# Presentation_PCB.net
KiCad netlist of a schematic drawn in EAGLE
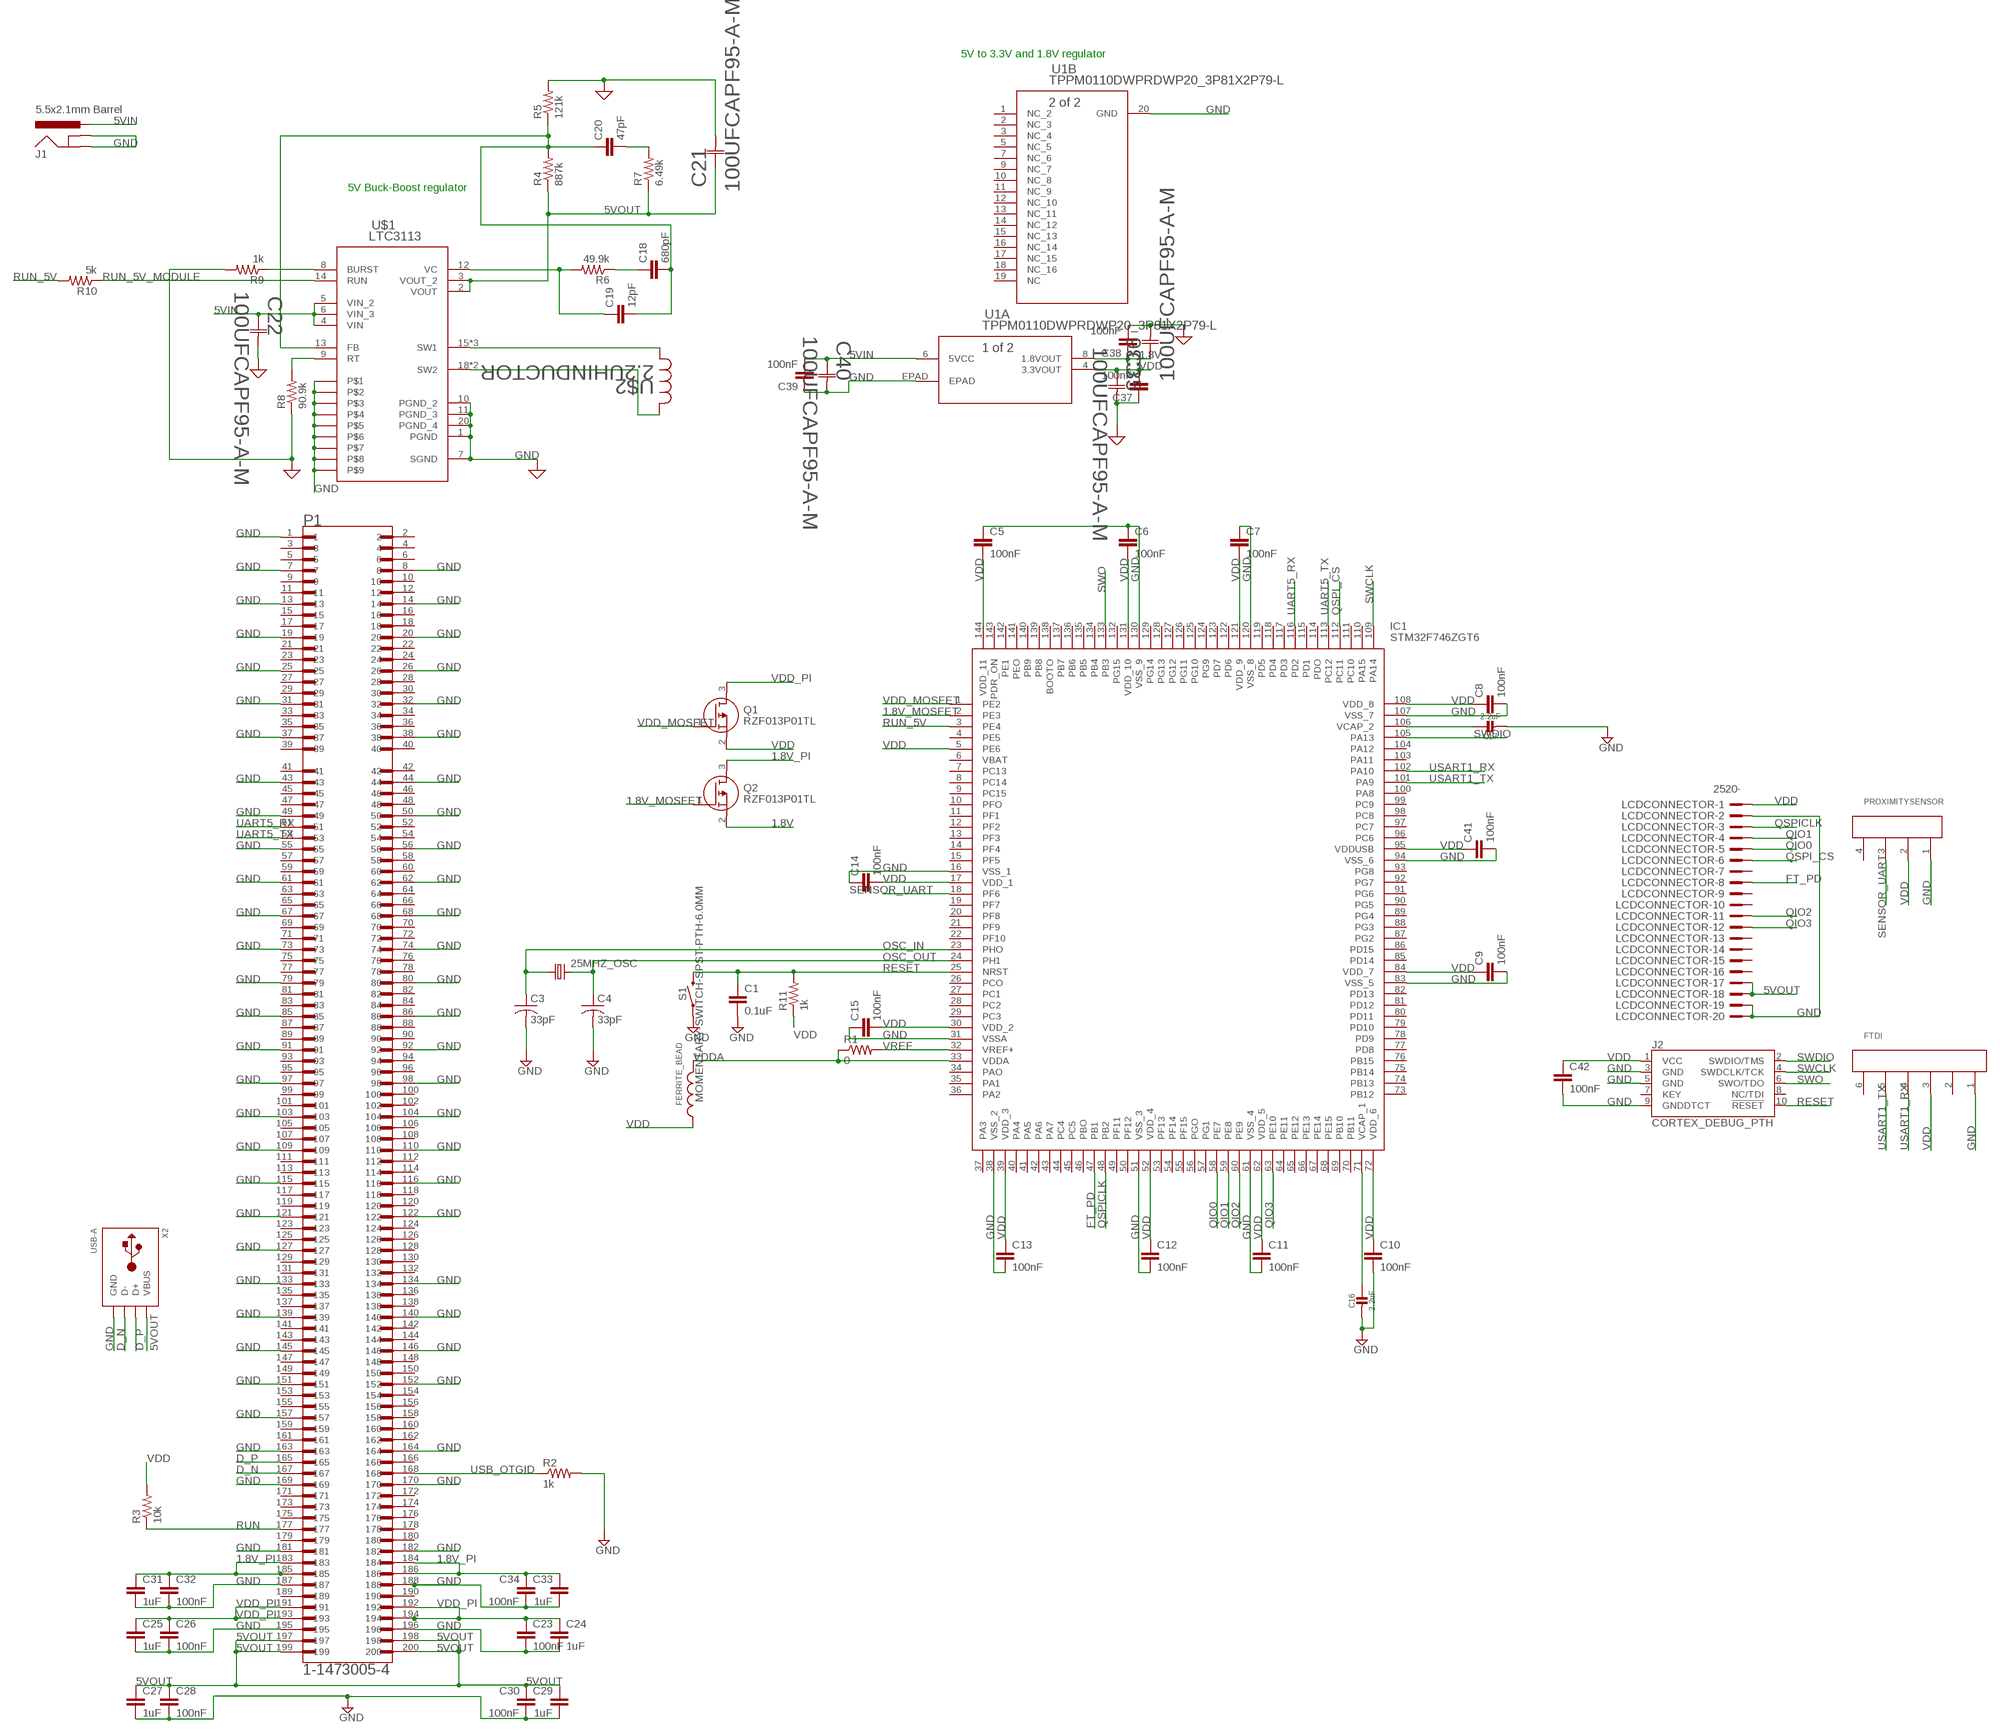
[diagram p0: schematic, sheet 1]

(export (version "E")
  (design (tool "Eeschema 10.0.6"))
  (components
    (comp (ref "25MHZ_OSC")
      (value "CRYSTALHC49UP")
      (footprint "eagle-import:HC49UP")
      (libsource (lib "eagle-import") (part "CRYSTALHC49UP"))
    )
    (comp (ref "C1")
      (value "0.1uF")
      (footprint "eagle-import:C0805")
      (libsource (lib "eagle-import") (part "C-EUC0805"))
    )
    (comp (ref "C3")
      (value "33pF")
      (footprint "eagle-import:C0805")
      (libsource (lib "eagle-import") (part "C-USC0805"))
    )
    (comp (ref "C4")
      (value "33pF")
      (footprint "eagle-import:C0805")
      (libsource (lib "eagle-import") (part "C-USC0805"))
    )
    (comp (ref "C5")
      (value "100nF")
      (footprint "eagle-import:C0805")
      (libsource (lib "eagle-import") (part "C-EUC0805"))
    )
    (comp (ref "C6")
      (value "100nF")
      (footprint "eagle-import:C0805")
      (libsource (lib "eagle-import") (part "C-EUC0805"))
    )
    (comp (ref "C7")
      (value "100nF")
      (footprint "eagle-import:C0805")
      (libsource (lib "eagle-import") (part "C-EUC0805"))
    )
    (comp (ref "C8")
      (value "100nF")
      (footprint "eagle-import:C0805")
      (libsource (lib "eagle-import") (part "C-EUC0805"))
    )
    (comp (ref "C9")
      (value "100nF")
      (footprint "eagle-import:C0805")
      (libsource (lib "eagle-import") (part "C-EUC0805"))
    )
    (comp (ref "C10")
      (value "100nF")
      (footprint "eagle-import:C0805")
      (libsource (lib "eagle-import") (part "C-EUC0805"))
    )
    (comp (ref "C11")
      (value "100nF")
      (footprint "eagle-import:C0805")
      (libsource (lib "eagle-import") (part "C-EUC0805"))
    )
    (comp (ref "C12")
      (value "100nF")
      (footprint "eagle-import:C0805")
      (libsource (lib "eagle-import") (part "C-EUC0805"))
    )
    (comp (ref "C13")
      (value "100nF")
      (footprint "eagle-import:C0805")
      (libsource (lib "eagle-import") (part "C-EUC0805"))
    )
    (comp (ref "C14")
      (value "100nF")
      (footprint "eagle-import:C0805")
      (libsource (lib "eagle-import") (part "C-EUC0805"))
    )
    (comp (ref "C15")
      (value "100nF")
      (footprint "eagle-import:C0805")
      (libsource (lib "eagle-import") (part "C-EUC0805"))
    )
    (comp (ref "C16")
      (value "2.2uF")
      (footprint "eagle-import:0805-NO")
      (libsource (lib "eagle-import") (part "CAP_CERAMIC0805-NOOUTLINE"))
    )
    (comp (ref "C17")
      (value "2.2uF")
      (footprint "eagle-import:0805-NO")
      (libsource (lib "eagle-import") (part "CAP_CERAMIC0805-NOOUTLINE"))
    )
    (comp (ref "C18")
      (value "680pF")
      (footprint "eagle-import:C0805")
      (libsource (lib "eagle-import") (part "C-EUC0805"))
    )
    (comp (ref "C19")
      (value "12pF")
      (footprint "eagle-import:C0805")
      (libsource (lib "eagle-import") (part "C-EUC0805"))
    )
    (comp (ref "C20")
      (value "47pF")
      (footprint "eagle-import:C0805")
      (libsource (lib "eagle-import") (part "C-EUC0805"))
    )
    (comp (ref "C21")
      (value "100UFCAPF95-A-M")
      (footprint "eagle-import:F95-A-M")
      (fields (field (name "MANUFACTURER_PART_NUMBER") "F951A107KAAAQ2"))
      (libsource (lib "eagle-import") (part "100UFCAPF95-A-M"))
    )
    (comp (ref "C22")
      (value "100UFCAPF95-A-M")
      (footprint "eagle-import:F95-A-M")
      (fields (field (name "MANUFACTURER_PART_NUMBER") "F951A107KAAAQ2"))
      (libsource (lib "eagle-import") (part "100UFCAPF95-A-M"))
    )
    (comp (ref "C23")
      (value "100nF")
      (footprint "eagle-import:C0805")
      (libsource (lib "eagle-import") (part "C-EUC0805"))
    )
    (comp (ref "C24")
      (value "1uF")
      (footprint "eagle-import:C0805")
      (libsource (lib "eagle-import") (part "C-EUC0805"))
    )
    (comp (ref "C25")
      (value "1uF")
      (footprint "eagle-import:C0805")
      (libsource (lib "eagle-import") (part "C-EUC0805"))
    )
    (comp (ref "C26")
      (value "100nF")
      (footprint "eagle-import:C0805")
      (libsource (lib "eagle-import") (part "C-EUC0805"))
    )
    (comp (ref "C27")
      (value "1uF")
      (footprint "eagle-import:C0805")
      (libsource (lib "eagle-import") (part "C-EUC0805"))
    )
    (comp (ref "C28")
      (value "100nF")
      (footprint "eagle-import:C0805")
      (libsource (lib "eagle-import") (part "C-EUC0805"))
    )
    (comp (ref "C29")
      (value "1uF")
      (footprint "eagle-import:C0805")
      (libsource (lib "eagle-import") (part "C-EUC0805"))
    )
    (comp (ref "C30")
      (value "100nF")
      (footprint "eagle-import:C0805")
      (libsource (lib "eagle-import") (part "C-EUC0805"))
    )
    (comp (ref "C31")
      (value "1uF")
      (footprint "eagle-import:C0805")
      (libsource (lib "eagle-import") (part "C-EUC0805"))
    )
    (comp (ref "C32")
      (value "100nF")
      (footprint "eagle-import:C0805")
      (libsource (lib "eagle-import") (part "C-EUC0805"))
    )
    (comp (ref "C33")
      (value "1uF")
      (footprint "eagle-import:C0805")
      (libsource (lib "eagle-import") (part "C-EUC0805"))
    )
    (comp (ref "C34")
      (value "100nF")
      (footprint "eagle-import:C0805")
      (libsource (lib "eagle-import") (part "C-EUC0805"))
    )
    (comp (ref "C35")
      (value "100UFCAPF95-A-M")
      (footprint "eagle-import:F95-A-M")
      (fields (field (name "MANUFACTURER_PART_NUMBER") "F951A107KAAAQ2"))
      (libsource (lib "eagle-import") (part "100UFCAPF95-A-M"))
    )
    (comp (ref "C36")
      (value "100UFCAPF95-A-M")
      (footprint "eagle-import:F95-A-M")
      (fields (field (name "MANUFACTURER_PART_NUMBER") "F951A107KAAAQ2"))
      (libsource (lib "eagle-import") (part "100UFCAPF95-A-M"))
    )
    (comp (ref "C37")
      (value "100nF")
      (footprint "eagle-import:C0805")
      (libsource (lib "eagle-import") (part "C-EUC0805"))
    )
    (comp (ref "C38")
      (value "100nF")
      (footprint "eagle-import:C0805")
      (libsource (lib "eagle-import") (part "C-EUC0805"))
    )
    (comp (ref "C39")
      (value "100nF")
      (footprint "eagle-import:C0805")
      (libsource (lib "eagle-import") (part "C-EUC0805"))
    )
    (comp (ref "C40")
      (value "100UFCAPF95-A-M")
      (footprint "eagle-import:F95-A-M")
      (fields (field (name "MANUFACTURER_PART_NUMBER") "F951A107KAAAQ2"))
      (libsource (lib "eagle-import") (part "100UFCAPF95-A-M"))
    )
    (comp (ref "C41")
      (value "100nF")
      (footprint "eagle-import:C0805")
      (libsource (lib "eagle-import") (part "C-EUC0805"))
    )
    (comp (ref "C42")
      (value "100nF")
      (footprint "eagle-import:C0805")
      (libsource (lib "eagle-import") (part "C-EUC0805"))
    )
    (comp (ref "FERRITE_BEAD")
      (value "WE-CBA_0805_782853112_HC")
      (footprint "eagle-import:WE-CBA_0805(W=4)")
      (libsource (lib "eagle-import") (part "WE-CBA_0805_HC_782853112"))
    )
    (comp (ref "FTDI")
      (value "66100611622")
      (footprint "eagle-import:66100611622")
      (libsource (lib "eagle-import") (part "66100611622"))
    )
    (comp (ref "IC1")
      (value "STM32F746ZGT6")
      (footprint "eagle-import:QFP50P2200X2200X160-144N")
      (fields
        (field (name "MOUSER_PART_NUMBER") "511-STM32F746ZGT6")
        (field (name "RS_PART_NUMBER") "8820290")
      )
      (libsource (lib "eagle-import") (part "STM32F746ZGT6"))
    )
    (comp (ref "J1")
      (value "5.5x2.1mm Barrel")
      (footprint "eagle-import:POWER_JACK_SMD")
      (libsource (lib "eagle-import") (part "POWER_JACKSMD"))
    )
    (comp (ref "J2")
      (value "CORTEX_DEBUG_PTH")
      (footprint "eagle-import:2X5-PTH-1.27MM")
      (libsource (lib "eagle-import") (part "CORTEX_DEBUG_PTH"))
    )
    (comp (ref "LCDCONNECTOR")
      (value "2520-")
      (footprint "eagle-import:PAK100_2500-20")
      (libsource (lib "eagle-import") (part "2520-"))
    )
    (comp (ref "P1")
      (value "1-1473005-4")
      (footprint "eagle-import:TE_1-1473005-4")
      (fields (field (name "MF") "TE Connectivity"))
      (libsource (lib "eagle-import") (part "1-1473005-4"))
    )
    (comp (ref "PROXIMITYSENSOR")
      (value "66100411622")
      (footprint "eagle-import:66100411622")
      (libsource (lib "eagle-import") (part "66100411622"))
    )
    (comp (ref "Q1")
      (value "RZF013P01TL")
      (footprint "eagle-import:SOT65P210X85-3N")
      (fields (field (name "MOUSER_PART_NUMBER") "755-RZF013P01TL"))
      (libsource (lib "eagle-import") (part "RZF013P01TL"))
    )
    (comp (ref "Q2")
      (value "RZF013P01TL")
      (footprint "eagle-import:SOT65P210X85-3N")
      (fields (field (name "MOUSER_PART_NUMBER") "755-RZF013P01TL"))
      (libsource (lib "eagle-import") (part "RZF013P01TL"))
    )
    (comp (ref "R1")
      (value "0")
      (footprint "eagle-import:R0805")
      (libsource (lib "eagle-import") (part "R-US_R0805"))
    )
    (comp (ref "R2")
      (value "1k")
      (footprint "eagle-import:R0805")
      (libsource (lib "eagle-import") (part "R-US_R0805"))
    )
    (comp (ref "R3")
      (value "10k")
      (footprint "eagle-import:R0805")
      (libsource (lib "eagle-import") (part "R-US_R0805"))
    )
    (comp (ref "R4")
      (value "887k")
      (footprint "eagle-import:R0805")
      (libsource (lib "eagle-import") (part "resistor_348_R-US_R0805"))
    )
    (comp (ref "R5")
      (value "121k")
      (footprint "eagle-import:R0805")
      (libsource (lib "eagle-import") (part "resistor_348_R-US_R0805"))
    )
    (comp (ref "R6")
      (value "49.9k")
      (footprint "eagle-import:R0805")
      (libsource (lib "eagle-import") (part "resistor_348_R-US_R0805"))
    )
    (comp (ref "R7")
      (value "6.49k")
      (footprint "eagle-import:R0805")
      (libsource (lib "eagle-import") (part "resistor_348_R-US_R0805"))
    )
    (comp (ref "R8")
      (value "90.9k")
      (footprint "eagle-import:R0805")
      (libsource (lib "eagle-import") (part "resistor_348_R-US_R0805"))
    )
    (comp (ref "R9")
      (value "1k")
      (footprint "eagle-import:R0805")
      (libsource (lib "eagle-import") (part "resistor_348_R-US_R0805"))
    )
    (comp (ref "R10")
      (value "5k")
      (footprint "eagle-import:R0805")
      (libsource (lib "eagle-import") (part "resistor_348_R-US_R0805"))
    )
    (comp (ref "R11")
      (value "1k")
      (footprint "eagle-import:R0805")
      (libsource (lib "eagle-import") (part "R-US_R0805"))
    )
    (comp (ref "S1")
      (value "MOMENTARY-SWITCH-SPST-PTH-6.0MM")
      (footprint "eagle-import:TACTILE_SWITCH_PTH_6.0MM")
      (libsource (lib "eagle-import") (part "MOMENTARY-SWITCH-SPST-PTH-6.0MM"))
    )
    (comp (ref "U$1")
      (value "LTC3113")
      (footprint "eagle-import:TSSOP-20_FE_CA")
      (libsource (lib "eagle-import") (part "LTC3113"))
    )
    (comp (ref "U$2")
      (value "2.2UHINDUCTOR")
      (footprint "eagle-import:IND_10040")
      (libsource (lib "eagle-import") (part "2.2UHINDUCTOR"))
    )
    (comp (ref "U1")
      (value "TPPM0110DWPRDWP20_3P81X2P79-L")
      (footprint "eagle-import:DWP20_3P81X2P79-L")
      (fields (field (name "MANUFACTURER_PART_NUMBER") "TPPM0110DWPR"))
      (libsource (lib "eagle-import") (part "TPPM0110DWPRDWP20_3P81X2P79-L"))
    )
    (comp (ref "X2")
      (value "USB-A")
      (footprint "eagle-import:MOLEX_480371000")
      (libsource (lib "eagle-import") (part "USB-A"))
    )
  )
  (nets
    (net (code "1") (name "/1.8V") (class "Default")
      (node (ref "C36") (pin "1") (pinfunction "1_1") (pintype "passive"))
      (node (ref "C38") (pin "1") (pinfunction "1_1") (pintype "passive"))
      (node (ref "Q2") (pin "2") (pinfunction "S_2") (pintype "bidirectional"))
      (node (ref "U1") (pin "8") (pinfunction "1.8VOUT_8") (pintype "output"))
    )
    (net (code "2") (name "/1.8V_MOSFET") (class "Default")
      (node (ref "IC1") (pin "2") (pinfunction "PE3_2") (pintype "bidirectional"))
      (node (ref "Q2") (pin "1") (pinfunction "G_1") (pintype "bidirectional"))
    )
    (net (code "3") (name "/1.8V_PI") (class "Default")
      (node (ref "C31") (pin "1") (pinfunction "1_1") (pintype "passive"))
      (node (ref "C32") (pin "1") (pinfunction "1_1") (pintype "passive"))
      (node (ref "C33") (pin "1") (pinfunction "1_1") (pintype "passive"))
      (node (ref "C34") (pin "1") (pinfunction "1_1") (pintype "passive"))
      (node (ref "P1") (pin "183") (pinfunction "183_183") (pintype "passive"))
      (node (ref "P1") (pin "184") (pinfunction "184_184") (pintype "passive"))
      (node (ref "P1") (pin "185") (pinfunction "185_185") (pintype "passive"))
      (node (ref "P1") (pin "186") (pinfunction "186_186") (pintype "passive"))
      (node (ref "Q2") (pin "3") (pinfunction "D_3") (pintype "bidirectional"))
    )
    (net (code "4") (name "/5VIN") (class "Default")
      (node (ref "C22") (pin "1") (pinfunction "1_1") (pintype "passive"))
      (node (ref "C39") (pin "2") (pinfunction "2_2") (pintype "passive"))
      (node (ref "C40") (pin "1") (pinfunction "1_1") (pintype "passive"))
      (node (ref "J1") (pin "VIN0") (pinfunction "PWR_VIN0") (pintype "bidirectional"))
      (node (ref "U$1") (pin "4") (pinfunction "VIN_4") (pintype "passive"))
      (node (ref "U$1") (pin "5") (pinfunction "VIN_2_5") (pintype "passive"))
      (node (ref "U$1") (pin "6") (pinfunction "VIN_3_6") (pintype "passive"))
      (node (ref "U1") (pin "6") (pinfunction "5VCC_6") (pintype "input"))
    )
    (net (code "5") (name "/5VOUT") (class "Default")
      (node (ref "C21") (pin "1") (pinfunction "1_1") (pintype "passive"))
      (node (ref "C27") (pin "1") (pinfunction "1_1") (pintype "passive"))
      (node (ref "C28") (pin "1") (pinfunction "1_1") (pintype "passive"))
      (node (ref "C29") (pin "1") (pinfunction "1_1") (pintype "passive"))
      (node (ref "C30") (pin "1") (pinfunction "1_1") (pintype "passive"))
      (node (ref "LCDCONNECTOR") (pin "17") (pinfunction "KL_17") (pintype "passive"))
      (node (ref "LCDCONNECTOR") (pin "18") (pinfunction "KL_18") (pintype "passive"))
      (node (ref "P1") (pin "197") (pinfunction "197_197") (pintype "passive"))
      (node (ref "P1") (pin "198") (pinfunction "198_198") (pintype "passive"))
      (node (ref "P1") (pin "199") (pinfunction "199_199") (pintype "passive"))
      (node (ref "P1") (pin "200") (pinfunction "200_200") (pintype "passive"))
      (node (ref "R4") (pin "1") (pinfunction "1_1") (pintype "passive"))
      (node (ref "R7") (pin "1") (pinfunction "1_1") (pintype "passive"))
      (node (ref "U$1") (pin "2") (pinfunction "VOUT_2") (pintype "passive"))
      (node (ref "U$1") (pin "3") (pinfunction "VOUT_2_3") (pintype "passive"))
      (node (ref "X2") (pin "1") (pinfunction "VBUS_1") (pintype "power_in"))
    )
    (net (code "6") (name "/D_N") (class "Default")
      (node (ref "P1") (pin "167") (pinfunction "167_167") (pintype "passive"))
      (node (ref "X2") (pin "2") (pinfunction "D-_2") (pintype "bidirectional"))
    )
    (net (code "7") (name "/D_P") (class "Default")
      (node (ref "P1") (pin "165") (pinfunction "165_165") (pintype "passive"))
      (node (ref "X2") (pin "3") (pinfunction "D+_3") (pintype "bidirectional"))
    )
    (net (code "8") (name "/FT_PD") (class "Default")
      (node (ref "IC1") (pin "47") (pinfunction "PB1_47") (pintype "bidirectional"))
      (node (ref "LCDCONNECTOR") (pin "8") (pinfunction "KL_8") (pintype "passive"))
    )
    (net (code "9") (name "/OSC_IN") (class "Default")
      (node (ref "25MHZ_OSC") (pin "1") (pinfunction "1_1") (pintype "passive"))
      (node (ref "C3") (pin "1") (pinfunction "1_1") (pintype "passive"))
      (node (ref "IC1") (pin "23") (pinfunction "PHO_23") (pintype "bidirectional"))
    )
    (net (code "10") (name "/OSC_OUT") (class "Default")
      (node (ref "25MHZ_OSC") (pin "2") (pinfunction "2_2") (pintype "passive"))
      (node (ref "C4") (pin "1") (pinfunction "1_1") (pintype "passive"))
      (node (ref "IC1") (pin "24") (pinfunction "PH1_24") (pintype "bidirectional"))
    )
    (net (code "11") (name "/QIO0") (class "Default")
      (node (ref "IC1") (pin "58") (pinfunction "PE7_58") (pintype "bidirectional"))
      (node (ref "LCDCONNECTOR") (pin "5") (pinfunction "KL_5") (pintype "passive"))
    )
    (net (code "12") (name "/QIO1") (class "Default")
      (node (ref "IC1") (pin "59") (pinfunction "PE8_59") (pintype "bidirectional"))
      (node (ref "LCDCONNECTOR") (pin "4") (pinfunction "KL_4") (pintype "passive"))
    )
    (net (code "13") (name "/QIO2") (class "Default")
      (node (ref "IC1") (pin "60") (pinfunction "PE9_60") (pintype "bidirectional"))
      (node (ref "LCDCONNECTOR") (pin "11") (pinfunction "KL_11") (pintype "passive"))
    )
    (net (code "14") (name "/QIO3") (class "Default")
      (node (ref "IC1") (pin "63") (pinfunction "PE10_63") (pintype "bidirectional"))
      (node (ref "LCDCONNECTOR") (pin "12") (pinfunction "KL_12") (pintype "passive"))
    )
    (net (code "15") (name "/QSPICLK") (class "Default")
      (node (ref "IC1") (pin "48") (pinfunction "PB2_48") (pintype "bidirectional"))
      (node (ref "LCDCONNECTOR") (pin "3") (pinfunction "KL_3") (pintype "passive"))
    )
    (net (code "16") (name "/QSPI_CS") (class "Default")
      (node (ref "IC1") (pin "112") (pinfunction "PC11_112") (pintype "bidirectional"))
      (node (ref "LCDCONNECTOR") (pin "6") (pinfunction "KL_6") (pintype "passive"))
    )
    (net (code "17") (name "/RESET") (class "Default")
      (node (ref "C1") (pin "1") (pinfunction "1_1") (pintype "passive"))
      (node (ref "IC1") (pin "25") (pinfunction "NRST_25") (pintype "input"))
      (node (ref "J2") (pin "10") (pinfunction "~{RESET}_10") (pintype "bidirectional"))
      (node (ref "R11") (pin "2") (pinfunction "2_2") (pintype "passive"))
      (node (ref "S1") (pin "3") (pinfunction "2_3") (pintype "passive"))
    )
    (net (code "18") (name "/RUN") (class "Default")
      (node (ref "P1") (pin "177") (pinfunction "177_177") (pintype "passive"))
      (node (ref "R3") (pin "1") (pinfunction "1_1") (pintype "passive"))
    )
    (net (code "19") (name "/RUN_5V") (class "Default")
      (node (ref "IC1") (pin "3") (pinfunction "PE4_3") (pintype "bidirectional"))
      (node (ref "R10") (pin "2") (pinfunction "2_2") (pintype "passive"))
    )
    (net (code "20") (name "/RUN_5V_MODULE") (class "Default")
      (node (ref "R10") (pin "1") (pinfunction "1_1") (pintype "passive"))
      (node (ref "U$1") (pin "14") (pinfunction "RUN_14") (pintype "passive"))
    )
    (net (code "21") (name "/SENSOR_UART") (class "Default")
      (node (ref "IC1") (pin "18") (pinfunction "PF6_18") (pintype "bidirectional"))
      (node (ref "PROXIMITYSENSOR") (pin "3") (pinfunction "3_3") (pintype "passive"))
    )
    (net (code "22") (name "/SWCLK") (class "Default")
      (node (ref "IC1") (pin "109") (pinfunction "PA14_109") (pintype "bidirectional"))
      (node (ref "J2") (pin "4") (pinfunction "SWDCLK/TCK_4") (pintype "bidirectional"))
    )
    (net (code "23") (name "/SWDIO") (class "Default")
      (node (ref "IC1") (pin "105") (pinfunction "PA13_105") (pintype "bidirectional"))
      (node (ref "J2") (pin "2") (pinfunction "SWDIO/TMS_2") (pintype "bidirectional"))
    )
    (net (code "24") (name "/SWO") (class "Default")
      (node (ref "IC1") (pin "133") (pinfunction "PB3_133") (pintype "bidirectional"))
      (node (ref "J2") (pin "6") (pinfunction "SWO/TDO_6") (pintype "bidirectional"))
    )
    (net (code "25") (name "/UART5_RX") (class "Default")
      (node (ref "IC1") (pin "116") (pinfunction "PD2_116") (pintype "bidirectional"))
      (node (ref "P1") (pin "51") (pinfunction "51_51") (pintype "passive"))
    )
    (net (code "26") (name "/UART5_TX") (class "Default")
      (node (ref "IC1") (pin "113") (pinfunction "PC12_113") (pintype "bidirectional"))
      (node (ref "P1") (pin "53") (pinfunction "53_53") (pintype "passive"))
    )
    (net (code "27") (name "/USART1_RX") (class "Default")
      (node (ref "FTDI") (pin "4") (pinfunction "4_4") (pintype "passive"))
      (node (ref "IC1") (pin "102") (pinfunction "PA10_102") (pintype "bidirectional"))
    )
    (net (code "28") (name "/USART1_TX") (class "Default")
      (node (ref "FTDI") (pin "5") (pinfunction "5_5") (pintype "passive"))
      (node (ref "IC1") (pin "101") (pinfunction "PA9_101") (pintype "bidirectional"))
    )
    (net (code "29") (name "/USB_OTGID") (class "Default")
      (node (ref "P1") (pin "168") (pinfunction "168_168") (pintype "passive"))
      (node (ref "R2") (pin "1") (pinfunction "1_1") (pintype "passive"))
    )
    (net (code "30") (name "/VDD") (class "Default")
      (node (ref "C10") (pin "1") (pinfunction "1_1") (pintype "passive"))
      (node (ref "C11") (pin "1") (pinfunction "1_1") (pintype "passive"))
      (node (ref "C12") (pin "1") (pinfunction "1_1") (pintype "passive"))
      (node (ref "C13") (pin "1") (pinfunction "1_1") (pintype "passive"))
      (node (ref "C14") (pin "2") (pinfunction "2_2") (pintype "passive"))
      (node (ref "C15") (pin "2") (pinfunction "2_2") (pintype "passive"))
      (node (ref "C35") (pin "1") (pinfunction "1_1") (pintype "passive"))
      (node (ref "C37") (pin "2") (pinfunction "2_2") (pintype "passive"))
      (node (ref "C41") (pin "1") (pinfunction "1_1") (pintype "passive"))
      (node (ref "C42") (pin "1") (pinfunction "1_1") (pintype "passive"))
      (node (ref "C5") (pin "2") (pinfunction "2_2") (pintype "passive"))
      (node (ref "C6") (pin "2") (pinfunction "2_2") (pintype "passive"))
      (node (ref "C7") (pin "2") (pinfunction "2_2") (pintype "passive"))
      (node (ref "C8") (pin "1") (pinfunction "1_1") (pintype "passive"))
      (node (ref "C9") (pin "1") (pinfunction "1_1") (pintype "passive"))
      (node (ref "FERRITE_BEAD") (pin "1") (pinfunction "1_1") (pintype "passive"))
      (node (ref "FTDI") (pin "3") (pinfunction "3_3") (pintype "passive"))
      (node (ref "IC1") (pin "108") (pinfunction "VDD_8_108") (pintype "power_in"))
      (node (ref "IC1") (pin "121") (pinfunction "VDD_9_121") (pintype "power_in"))
      (node (ref "IC1") (pin "131") (pinfunction "VDD_10_131") (pintype "power_in"))
      (node (ref "IC1") (pin "144") (pinfunction "VDD_11_144") (pintype "power_in"))
      (node (ref "IC1") (pin "17") (pinfunction "VDD_1_17") (pintype "power_in"))
      (node (ref "IC1") (pin "30") (pinfunction "VDD_2_30") (pintype "power_in"))
      (node (ref "IC1") (pin "39") (pinfunction "VDD_3_39") (pintype "power_in"))
      (node (ref "IC1") (pin "5") (pinfunction "PE6_5") (pintype "bidirectional"))
      (node (ref "IC1") (pin "52") (pinfunction "VDD_4_52") (pintype "power_in"))
      (node (ref "IC1") (pin "62") (pinfunction "VDD_5_62") (pintype "power_in"))
      (node (ref "IC1") (pin "72") (pinfunction "VDD_6_72") (pintype "power_in"))
      (node (ref "IC1") (pin "84") (pinfunction "VDD_7_84") (pintype "power_in"))
      (node (ref "IC1") (pin "95") (pinfunction "VDDUSB_95") (pintype "power_in"))
      (node (ref "J2") (pin "1") (pinfunction "VCC_1") (pintype "bidirectional"))
      (node (ref "LCDCONNECTOR") (pin "1") (pinfunction "KL_1") (pintype "passive"))
      (node (ref "PROXIMITYSENSOR") (pin "2") (pinfunction "2_2") (pintype "passive"))
      (node (ref "Q1") (pin "2") (pinfunction "S_2") (pintype "bidirectional"))
      (node (ref "R11") (pin "1") (pinfunction "1_1") (pintype "passive"))
      (node (ref "R3") (pin "2") (pinfunction "2_2") (pintype "passive"))
      (node (ref "U1") (pin "4") (pinfunction "3.3VOUT_4") (pintype "output"))
    )
    (net (code "31") (name "/VDDA") (class "Default")
      (node (ref "FERRITE_BEAD") (pin "2") (pinfunction "2_2") (pintype "passive"))
      (node (ref "IC1") (pin "33") (pinfunction "VDDA_33") (pintype "power_in"))
      (node (ref "R1") (pin "1") (pinfunction "1_1") (pintype "passive"))
    )
    (net (code "32") (name "/VDD_MOSFET") (class "Default")
      (node (ref "IC1") (pin "1") (pinfunction "PE2_1") (pintype "bidirectional"))
      (node (ref "Q1") (pin "1") (pinfunction "G_1") (pintype "bidirectional"))
    )
    (net (code "33") (name "/VDD_PI") (class "Default")
      (node (ref "C23") (pin "1") (pinfunction "1_1") (pintype "passive"))
      (node (ref "C24") (pin "1") (pinfunction "1_1") (pintype "passive"))
      (node (ref "C25") (pin "1") (pinfunction "1_1") (pintype "passive"))
      (node (ref "C26") (pin "1") (pinfunction "1_1") (pintype "passive"))
      (node (ref "P1") (pin "191") (pinfunction "191_191") (pintype "passive"))
      (node (ref "P1") (pin "192") (pinfunction "192_192") (pintype "passive"))
      (node (ref "P1") (pin "193") (pinfunction "193_193") (pintype "passive"))
      (node (ref "P1") (pin "194") (pinfunction "194_194") (pintype "passive"))
      (node (ref "Q1") (pin "3") (pinfunction "D_3") (pintype "bidirectional"))
    )
    (net (code "34") (name "/VREF") (class "Default")
      (node (ref "IC1") (pin "32") (pinfunction "VREF+_32") (pintype "input"))
      (node (ref "R1") (pin "2") (pinfunction "2_2") (pintype "passive"))
    )
    (net (code "35") (name "GND") (class "Default")
      (node (ref "C1") (pin "2") (pinfunction "2_2") (pintype "passive"))
      (node (ref "C10") (pin "2") (pinfunction "2_2") (pintype "passive"))
      (node (ref "C11") (pin "2") (pinfunction "2_2") (pintype "passive"))
      (node (ref "C12") (pin "2") (pinfunction "2_2") (pintype "passive"))
      (node (ref "C13") (pin "2") (pinfunction "2_2") (pintype "passive"))
      (node (ref "C14") (pin "1") (pinfunction "1_1") (pintype "passive"))
      (node (ref "C15") (pin "1") (pinfunction "1_1") (pintype "passive"))
      (node (ref "C16") (pin "2") (pinfunction "2_2") (pintype "passive"))
      (node (ref "C17") (pin "2") (pinfunction "2_2") (pintype "passive"))
      (node (ref "C21") (pin "2") (pinfunction "2_2") (pintype "passive"))
      (node (ref "C22") (pin "2") (pinfunction "2_2") (pintype "passive"))
      (node (ref "C23") (pin "2") (pinfunction "2_2") (pintype "passive"))
      (node (ref "C24") (pin "2") (pinfunction "2_2") (pintype "passive"))
      (node (ref "C25") (pin "2") (pinfunction "2_2") (pintype "passive"))
      (node (ref "C26") (pin "2") (pinfunction "2_2") (pintype "passive"))
      (node (ref "C27") (pin "2") (pinfunction "2_2") (pintype "passive"))
      (node (ref "C28") (pin "2") (pinfunction "2_2") (pintype "passive"))
      (node (ref "C29") (pin "2") (pinfunction "2_2") (pintype "passive"))
      (node (ref "C3") (pin "2") (pinfunction "2_2") (pintype "passive"))
      (node (ref "C30") (pin "2") (pinfunction "2_2") (pintype "passive"))
      (node (ref "C31") (pin "2") (pinfunction "2_2") (pintype "passive"))
      (node (ref "C32") (pin "2") (pinfunction "2_2") (pintype "passive"))
      (node (ref "C33") (pin "2") (pinfunction "2_2") (pintype "passive"))
      (node (ref "C34") (pin "2") (pinfunction "2_2") (pintype "passive"))
      (node (ref "C35") (pin "2") (pinfunction "2_2") (pintype "passive"))
      (node (ref "C36") (pin "2") (pinfunction "2_2") (pintype "passive"))
      (node (ref "C37") (pin "1") (pinfunction "1_1") (pintype "passive"))
      (node (ref "C38") (pin "2") (pinfunction "2_2") (pintype "passive"))
      (node (ref "C39") (pin "1") (pinfunction "1_1") (pintype "passive"))
      (node (ref "C4") (pin "2") (pinfunction "2_2") (pintype "passive"))
      (node (ref "C40") (pin "2") (pinfunction "2_2") (pintype "passive"))
      (node (ref "C41") (pin "2") (pinfunction "2_2") (pintype "passive"))
      (node (ref "C42") (pin "2") (pinfunction "2_2") (pintype "passive"))
      (node (ref "C5") (pin "1") (pinfunction "1_1") (pintype "passive"))
      (node (ref "C6") (pin "1") (pinfunction "1_1") (pintype "passive"))
      (node (ref "C7") (pin "1") (pinfunction "1_1") (pintype "passive"))
      (node (ref "C8") (pin "2") (pinfunction "2_2") (pintype "passive"))
      (node (ref "C9") (pin "2") (pinfunction "2_2") (pintype "passive"))
      (node (ref "FTDI") (pin "1") (pinfunction "1_1") (pintype "passive"))
      (node (ref "IC1") (pin "107") (pinfunction "VSS_7_107") (pintype "power_in"))
      (node (ref "IC1") (pin "120") (pinfunction "VSS_8_120") (pintype "power_in"))
      (node (ref "IC1") (pin "130") (pinfunction "VSS_9_130") (pintype "power_in"))
      (node (ref "IC1") (pin "16") (pinfunction "VSS_1_16") (pintype "power_in"))
      (node (ref "IC1") (pin "31") (pinfunction "VSSA_31") (pintype "power_in"))
      (node (ref "IC1") (pin "38") (pinfunction "VSS_2_38") (pintype "power_in"))
      (node (ref "IC1") (pin "51") (pinfunction "VSS_3_51") (pintype "power_in"))
      (node (ref "IC1") (pin "61") (pinfunction "VSS_4_61") (pintype "power_in"))
      (node (ref "IC1") (pin "83") (pinfunction "VSS_5_83") (pintype "power_in"))
      (node (ref "IC1") (pin "94") (pinfunction "VSS_6_94") (pintype "power_in"))
      (node (ref "J1") (pin "GND") (pinfunction "GNDBREAK_GND") (pintype "bidirectional"))
      (node (ref "J1") (pin "P$4") (pinfunction "GND_P$4") (pintype "bidirectional"))
      (node (ref "J2") (pin "3") (pinfunction "GND_3") (pintype "bidirectional"))
      (node (ref "J2") (pin "5") (pinfunction "GND_5") (pintype "bidirectional"))
      (node (ref "J2") (pin "9") (pinfunction "GNDDTCT_9") (pintype "bidirectional"))
      (node (ref "LCDCONNECTOR") (pin "19") (pinfunction "KL_19") (pintype "passive"))
      (node (ref "LCDCONNECTOR") (pin "2") (pinfunction "KL_2") (pintype "passive"))
      (node (ref "LCDCONNECTOR") (pin "20") (pinfunction "KL_20") (pintype "passive"))
      (node (ref "P1") (pin "1") (pinfunction "1_1") (pintype "passive"))
      (node (ref "P1") (pin "103") (pinfunction "103_103") (pintype "passive"))
      (node (ref "P1") (pin "104") (pinfunction "104_104") (pintype "passive"))
      (node (ref "P1") (pin "109") (pinfunction "109_109") (pintype "passive"))
      (node (ref "P1") (pin "110") (pinfunction "110_110") (pintype "passive"))
      (node (ref "P1") (pin "115") (pinfunction "115_115") (pintype "passive"))
      (node (ref "P1") (pin "116") (pinfunction "116_116") (pintype "passive"))
      (node (ref "P1") (pin "121") (pinfunction "121_121") (pintype "passive"))
      (node (ref "P1") (pin "122") (pinfunction "122_122") (pintype "passive"))
      (node (ref "P1") (pin "127") (pinfunction "127_127") (pintype "passive"))
      (node (ref "P1") (pin "13") (pinfunction "13_13") (pintype "passive"))
      (node (ref "P1") (pin "133") (pinfunction "133_133") (pintype "passive"))
      (node (ref "P1") (pin "134") (pinfunction "134_134") (pintype "passive"))
      (node (ref "P1") (pin "139") (pinfunction "139_139") (pintype "passive"))
      (node (ref "P1") (pin "14") (pinfunction "14_14") (pintype "passive"))
      (node (ref "P1") (pin "140") (pinfunction "140_140") (pintype "passive"))
      (node (ref "P1") (pin "145") (pinfunction "145_145") (pintype "passive"))
      (node (ref "P1") (pin "146") (pinfunction "146_146") (pintype "passive"))
      (node (ref "P1") (pin "151") (pinfunction "151_151") (pintype "passive"))
      (node (ref "P1") (pin "152") (pinfunction "152_152") (pintype "passive"))
      (node (ref "P1") (pin "157") (pinfunction "157_157") (pintype "passive"))
      (node (ref "P1") (pin "163") (pinfunction "163_163") (pintype "passive"))
      (node (ref "P1") (pin "164") (pinfunction "164_164") (pintype "passive"))
      (node (ref "P1") (pin "169") (pinfunction "169_169") (pintype "passive"))
      (node (ref "P1") (pin "170") (pinfunction "170_170") (pintype "passive"))
      (node (ref "P1") (pin "181") (pinfunction "181_181") (pintype "passive"))
      (node (ref "P1") (pin "182") (pinfunction "182_182") (pintype "passive"))
      (node (ref "P1") (pin "187") (pinfunction "187_187") (pintype "passive"))
      (node (ref "P1") (pin "188") (pinfunction "188_188") (pintype "passive"))
      (node (ref "P1") (pin "19") (pinfunction "19_19") (pintype "passive"))
      (node (ref "P1") (pin "195") (pinfunction "195_195") (pintype "passive"))
      (node (ref "P1") (pin "196") (pinfunction "196_196") (pintype "passive"))
      (node (ref "P1") (pin "20") (pinfunction "20_20") (pintype "passive"))
      (node (ref "P1") (pin "25") (pinfunction "25_25") (pintype "passive"))
      (node (ref "P1") (pin "26") (pinfunction "26_26") (pintype "passive"))
      (node (ref "P1") (pin "31") (pinfunction "31_31") (pintype "passive"))
      (node (ref "P1") (pin "32") (pinfunction "32_32") (pintype "passive"))
      (node (ref "P1") (pin "37") (pinfunction "37_37") (pintype "passive"))
      (node (ref "P1") (pin "38") (pinfunction "38_38") (pintype "passive"))
      (node (ref "P1") (pin "43") (pinfunction "43_43") (pintype "passive"))
      (node (ref "P1") (pin "44") (pinfunction "44_44") (pintype "passive"))
      (node (ref "P1") (pin "49") (pinfunction "49_49") (pintype "passive"))
      (node (ref "P1") (pin "50") (pinfunction "50_50") (pintype "passive"))
      (node (ref "P1") (pin "55") (pinfunction "55_55") (pintype "passive"))
      (node (ref "P1") (pin "56") (pinfunction "56_56") (pintype "passive"))
      (node (ref "P1") (pin "61") (pinfunction "61_61") (pintype "passive"))
      (node (ref "P1") (pin "62") (pinfunction "62_62") (pintype "passive"))
      (node (ref "P1") (pin "67") (pinfunction "67_67") (pintype "passive"))
      (node (ref "P1") (pin "68") (pinfunction "68_68") (pintype "passive"))
      (node (ref "P1") (pin "7") (pinfunction "7_7") (pintype "passive"))
      (node (ref "P1") (pin "73") (pinfunction "73_73") (pintype "passive"))
      (node (ref "P1") (pin "74") (pinfunction "74_74") (pintype "passive"))
      (node (ref "P1") (pin "79") (pinfunction "79_79") (pintype "passive"))
      (node (ref "P1") (pin "8") (pinfunction "8_8") (pintype "passive"))
      (node (ref "P1") (pin "80") (pinfunction "80_80") (pintype "passive"))
      (node (ref "P1") (pin "85") (pinfunction "85_85") (pintype "passive"))
      (node (ref "P1") (pin "86") (pinfunction "86_86") (pintype "passive"))
      (node (ref "P1") (pin "91") (pinfunction "91_91") (pintype "passive"))
      (node (ref "P1") (pin "92") (pinfunction "92_92") (pintype "passive"))
      (node (ref "P1") (pin "97") (pinfunction "97_97") (pintype "passive"))
      (node (ref "P1") (pin "98") (pinfunction "98_98") (pintype "passive"))
      (node (ref "PROXIMITYSENSOR") (pin "1") (pinfunction "1_1") (pintype "passive"))
      (node (ref "R2") (pin "2") (pinfunction "2_2") (pintype "passive"))
      (node (ref "R5") (pin "2") (pinfunction "2_2") (pintype "passive"))
      (node (ref "R8") (pin "1") (pinfunction "1_1") (pintype "passive"))
      (node (ref "R9") (pin "2") (pinfunction "2_2") (pintype "passive"))
      (node (ref "S1") (pin "1") (pinfunction "1_1") (pintype "passive"))
      (node (ref "U$1") (pin "1") (pinfunction "PGND_1") (pintype "passive"))
      (node (ref "U$1") (pin "10") (pinfunction "PGND_2_10") (pintype "passive"))
      (node (ref "U$1") (pin "11") (pinfunction "PGND_3_11") (pintype "passive"))
      (node (ref "U$1") (pin "20") (pinfunction "PGND_4_20") (pintype "passive"))
      (node (ref "U$1") (pin "7") (pinfunction "SGND_7") (pintype "passive"))
      (node (ref "U$1") (pin "P$1") (pinfunction "P$1_P$1") (pintype "passive"))
      (node (ref "U$1") (pin "P$2") (pinfunction "P$2_P$2") (pintype "passive"))
      (node (ref "U$1") (pin "P$3") (pinfunction "P$3_P$3") (pintype "passive"))
      (node (ref "U$1") (pin "P$4") (pinfunction "P$4_P$4") (pintype "passive"))
      (node (ref "U$1") (pin "P$5") (pinfunction "P$5_P$5") (pintype "passive"))
      (node (ref "U$1") (pin "P$6") (pinfunction "P$6_P$6") (pintype "passive"))
      (node (ref "U$1") (pin "P$7") (pinfunction "P$7_P$7") (pintype "passive"))
      (node (ref "U$1") (pin "P$8") (pinfunction "P$8_P$8") (pintype "passive"))
      (node (ref "U$1") (pin "P$9") (pinfunction "P$9_P$9") (pintype "passive"))
      (node (ref "U1") (pin "20") (pinfunction "GND_20") (pintype "power_in"))
      (node (ref "U1") (pin "EPAD") (pinfunction "EPAD_EPAD") (pintype "passive"))
      (node (ref "X2") (pin "4") (pinfunction "GND_4") (pintype "power_in"))
    )
    (net (code "36") (name "Net-(C18-Pad1)") (class "Default")
      (node (ref "C18") (pin "1") (pinfunction "1_1") (pintype "passive"))
      (node (ref "R6") (pin "1") (pinfunction "1_1") (pintype "passive"))
    )
    (net (code "37") (name "Net-(C20-Pad2)") (class "Default")
      (node (ref "C20") (pin "2") (pinfunction "2_2") (pintype "passive"))
      (node (ref "R7") (pin "2") (pinfunction "2_2") (pintype "passive"))
    )
    (net (code "38") (name "Net-(IC1-VCAP_1)") (class "Default")
      (node (ref "C16") (pin "1") (pinfunction "1_1") (pintype "passive"))
      (node (ref "IC1") (pin "71") (pinfunction "VCAP_1_71") (pintype "bidirectional"))
    )
    (net (code "39") (name "Net-(IC1-VCAP_2)") (class "Default")
      (node (ref "C17") (pin "1") (pinfunction "1_1") (pintype "passive"))
      (node (ref "IC1") (pin "106") (pinfunction "VCAP_2_106") (pintype "bidirectional"))
    )
    (net (code "40") (name "Net-(U$1-BURST)") (class "Default")
      (node (ref "R9") (pin "1") (pinfunction "1_1") (pintype "passive"))
      (node (ref "U$1") (pin "8") (pinfunction "BURST_8") (pintype "passive"))
    )
    (net (code "41") (name "Net-(U$1-FB)") (class "Default")
      (node (ref "C18") (pin "2") (pinfunction "2_2") (pintype "passive"))
      (node (ref "C19") (pin "2") (pinfunction "2_2") (pintype "passive"))
      (node (ref "C20") (pin "1") (pinfunction "1_1") (pintype "passive"))
      (node (ref "R4") (pin "2") (pinfunction "2_2") (pintype "passive"))
      (node (ref "R5") (pin "1") (pinfunction "1_1") (pintype "passive"))
      (node (ref "U$1") (pin "13") (pinfunction "FB_13") (pintype "passive"))
    )
    (net (code "42") (name "Net-(U$1-RT)") (class "Default")
      (node (ref "R8") (pin "2") (pinfunction "2_2") (pintype "passive"))
      (node (ref "U$1") (pin "9") (pinfunction "RT_9") (pintype "passive"))
    )
    (net (code "43") (name "Net-(U$1-SW1-Pad15)") (class "Default")
      (node (ref "U$1") (pin "15") (pinfunction "SW1_15") (pintype "passive"))
      (node (ref "U$1") (pin "16") (pinfunction "SW1_16") (pintype "passive"))
      (node (ref "U$1") (pin "17") (pinfunction "SW1_17") (pintype "passive"))
      (node (ref "U$2") (pin "2") (pinfunction "2_2") (pintype "passive"))
    )
    (net (code "44") (name "Net-(U$1-SW2-Pad18)") (class "Default")
      (node (ref "U$1") (pin "18") (pinfunction "SW2_18") (pintype "passive"))
      (node (ref "U$1") (pin "19") (pinfunction "SW2_19") (pintype "passive"))
      (node (ref "U$2") (pin "1") (pinfunction "1_1") (pintype "passive"))
    )
    (net (code "45") (name "Net-(U$1-VC)") (class "Default")
      (node (ref "C19") (pin "1") (pinfunction "1_1") (pintype "passive"))
      (node (ref "R6") (pin "2") (pinfunction "2_2") (pintype "passive"))
      (node (ref "U$1") (pin "12") (pinfunction "VC_12") (pintype "passive"))
    )
    (net (code "46") (name "unconnected-(FTDI-Pad2)") (class "Default")
      (node (ref "FTDI") (pin "2") (pinfunction "2_2") (pintype "passive"))
    )
    (net (code "47") (name "unconnected-(FTDI-Pad6)") (class "Default")
      (node (ref "FTDI") (pin "6") (pinfunction "6_6") (pintype "passive"))
    )
    (net (code "48") (name "unconnected-(IC1-BOOTO-Pad138)") (class "Default")
      (node (ref "IC1") (pin "138") (pinfunction "BOOTO_138") (pintype "bidirectional"))
    )
    (net (code "49") (name "unconnected-(IC1-PA1-Pad35)") (class "Default")
      (node (ref "IC1") (pin "35") (pinfunction "PA1_35") (pintype "bidirectional"))
    )
    (net (code "50") (name "unconnected-(IC1-PA2-Pad36)") (class "Default")
      (node (ref "IC1") (pin "36") (pinfunction "PA2_36") (pintype "bidirectional"))
    )
    (net (code "51") (name "unconnected-(IC1-PA3-Pad37)") (class "Default")
      (node (ref "IC1") (pin "37") (pinfunction "PA3_37") (pintype "bidirectional"))
    )
    (net (code "52") (name "unconnected-(IC1-PA4-Pad40)") (class "Default")
      (node (ref "IC1") (pin "40") (pinfunction "PA4_40") (pintype "bidirectional"))
    )
    (net (code "53") (name "unconnected-(IC1-PA5-Pad41)") (class "Default")
      (node (ref "IC1") (pin "41") (pinfunction "PA5_41") (pintype "bidirectional"))
    )
    (net (code "54") (name "unconnected-(IC1-PA6-Pad42)") (class "Default")
      (node (ref "IC1") (pin "42") (pinfunction "PA6_42") (pintype "bidirectional"))
    )
    (net (code "55") (name "unconnected-(IC1-PA7-Pad43)") (class "Default")
      (node (ref "IC1") (pin "43") (pinfunction "PA7_43") (pintype "bidirectional"))
    )
    (net (code "56") (name "unconnected-(IC1-PA8-Pad100)") (class "Default")
      (node (ref "IC1") (pin "100") (pinfunction "PA8_100") (pintype "bidirectional"))
    )
    (net (code "57") (name "unconnected-(IC1-PA11-Pad103)") (class "Default")
      (node (ref "IC1") (pin "103") (pinfunction "PA11_103") (pintype "bidirectional"))
    )
    (net (code "58") (name "unconnected-(IC1-PA12-Pad104)") (class "Default")
      (node (ref "IC1") (pin "104") (pinfunction "PA12_104") (pintype "bidirectional"))
    )
    (net (code "59") (name "unconnected-(IC1-PA15-Pad110)") (class "Default")
      (node (ref "IC1") (pin "110") (pinfunction "PA15_110") (pintype "bidirectional"))
    )
    (net (code "60") (name "unconnected-(IC1-PAO-Pad34)") (class "Default")
      (node (ref "IC1") (pin "34") (pinfunction "PAO_34") (pintype "bidirectional"))
    )
    (net (code "61") (name "unconnected-(IC1-PB4-Pad134)") (class "Default")
      (node (ref "IC1") (pin "134") (pinfunction "PB4_134") (pintype "bidirectional"))
    )
    (net (code "62") (name "unconnected-(IC1-PB5-Pad135)") (class "Default")
      (node (ref "IC1") (pin "135") (pinfunction "PB5_135") (pintype "bidirectional"))
    )
    (net (code "63") (name "unconnected-(IC1-PB6-Pad136)") (class "Default")
      (node (ref "IC1") (pin "136") (pinfunction "PB6_136") (pintype "bidirectional"))
    )
    (net (code "64") (name "unconnected-(IC1-PB7-Pad137)") (class "Default")
      (node (ref "IC1") (pin "137") (pinfunction "PB7_137") (pintype "bidirectional"))
    )
    (net (code "65") (name "unconnected-(IC1-PB8-Pad139)") (class "Default")
      (node (ref "IC1") (pin "139") (pinfunction "PB8_139") (pintype "bidirectional"))
    )
    (net (code "66") (name "unconnected-(IC1-PB9-Pad140)") (class "Default")
      (node (ref "IC1") (pin "140") (pinfunction "PB9_140") (pintype "bidirectional"))
    )
    (net (code "67") (name "unconnected-(IC1-PB10-Pad69)") (class "Default")
      (node (ref "IC1") (pin "69") (pinfunction "PB10_69") (pintype "bidirectional"))
    )
    (net (code "68") (name "unconnected-(IC1-PB11-Pad70)") (class "Default")
      (node (ref "IC1") (pin "70") (pinfunction "PB11_70") (pintype "bidirectional"))
    )
    (net (code "69") (name "unconnected-(IC1-PB12-Pad73)") (class "Default")
      (node (ref "IC1") (pin "73") (pinfunction "PB12_73") (pintype "bidirectional"))
    )
    (net (code "70") (name "unconnected-(IC1-PB13-Pad74)") (class "Default")
      (node (ref "IC1") (pin "74") (pinfunction "PB13_74") (pintype "bidirectional"))
    )
    (net (code "71") (name "unconnected-(IC1-PB14-Pad75)") (class "Default")
      (node (ref "IC1") (pin "75") (pinfunction "PB14_75") (pintype "bidirectional"))
    )
    (net (code "72") (name "unconnected-(IC1-PB15-Pad76)") (class "Default")
      (node (ref "IC1") (pin "76") (pinfunction "PB15_76") (pintype "bidirectional"))
    )
    (net (code "73") (name "unconnected-(IC1-PBO-Pad46)") (class "Default")
      (node (ref "IC1") (pin "46") (pinfunction "PBO_46") (pintype "bidirectional"))
    )
    (net (code "74") (name "unconnected-(IC1-PC1-Pad27)") (class "Default")
      (node (ref "IC1") (pin "27") (pinfunction "PC1_27") (pintype "bidirectional"))
    )
    (net (code "75") (name "unconnected-(IC1-PC2-Pad28)") (class "Default")
      (node (ref "IC1") (pin "28") (pinfunction "PC2_28") (pintype "bidirectional"))
    )
    (net (code "76") (name "unconnected-(IC1-PC3-Pad29)") (class "Default")
      (node (ref "IC1") (pin "29") (pinfunction "PC3_29") (pintype "bidirectional"))
    )
    (net (code "77") (name "unconnected-(IC1-PC4-Pad44)") (class "Default")
      (node (ref "IC1") (pin "44") (pinfunction "PC4_44") (pintype "bidirectional"))
    )
    (net (code "78") (name "unconnected-(IC1-PC5-Pad45)") (class "Default")
      (node (ref "IC1") (pin "45") (pinfunction "PC5_45") (pintype "bidirectional"))
    )
    (net (code "79") (name "unconnected-(IC1-PC6-Pad96)") (class "Default")
      (node (ref "IC1") (pin "96") (pinfunction "PC6_96") (pintype "bidirectional"))
    )
    (net (code "80") (name "unconnected-(IC1-PC7-Pad97)") (class "Default")
      (node (ref "IC1") (pin "97") (pinfunction "PC7_97") (pintype "bidirectional"))
    )
    (net (code "81") (name "unconnected-(IC1-PC8-Pad98)") (class "Default")
      (node (ref "IC1") (pin "98") (pinfunction "PC8_98") (pintype "bidirectional"))
    )
    (net (code "82") (name "unconnected-(IC1-PC9-Pad99)") (class "Default")
      (node (ref "IC1") (pin "99") (pinfunction "PC9_99") (pintype "bidirectional"))
    )
    (net (code "83") (name "unconnected-(IC1-PC10-Pad111)") (class "Default")
      (node (ref "IC1") (pin "111") (pinfunction "PC10_111") (pintype "bidirectional"))
    )
    (net (code "84") (name "unconnected-(IC1-PC13-Pad7)") (class "Default")
      (node (ref "IC1") (pin "7") (pinfunction "PC13_7") (pintype "bidirectional"))
    )
    (net (code "85") (name "unconnected-(IC1-PC14-Pad8)") (class "Default")
      (node (ref "IC1") (pin "8") (pinfunction "PC14_8") (pintype "bidirectional"))
    )
    (net (code "86") (name "unconnected-(IC1-PC15-Pad9)") (class "Default")
      (node (ref "IC1") (pin "9") (pinfunction "PC15_9") (pintype "bidirectional"))
    )
    (net (code "87") (name "unconnected-(IC1-PCO-Pad26)") (class "Default")
      (node (ref "IC1") (pin "26") (pinfunction "PCO_26") (pintype "bidirectional"))
    )
    (net (code "88") (name "unconnected-(IC1-PD1-Pad115)") (class "Default")
      (node (ref "IC1") (pin "115") (pinfunction "PD1_115") (pintype "bidirectional"))
    )
    (net (code "89") (name "unconnected-(IC1-PD3-Pad117)") (class "Default")
      (node (ref "IC1") (pin "117") (pinfunction "PD3_117") (pintype "bidirectional"))
    )
    (net (code "90") (name "unconnected-(IC1-PD4-Pad118)") (class "Default")
      (node (ref "IC1") (pin "118") (pinfunction "PD4_118") (pintype "bidirectional"))
    )
    (net (code "91") (name "unconnected-(IC1-PD5-Pad119)") (class "Default")
      (node (ref "IC1") (pin "119") (pinfunction "PD5_119") (pintype "bidirectional"))
    )
    (net (code "92") (name "unconnected-(IC1-PD6-Pad122)") (class "Default")
      (node (ref "IC1") (pin "122") (pinfunction "PD6_122") (pintype "bidirectional"))
    )
    (net (code "93") (name "unconnected-(IC1-PD7-Pad123)") (class "Default")
      (node (ref "IC1") (pin "123") (pinfunction "PD7_123") (pintype "bidirectional"))
    )
    (net (code "94") (name "unconnected-(IC1-PD8-Pad77)") (class "Default")
      (node (ref "IC1") (pin "77") (pinfunction "PD8_77") (pintype "bidirectional"))
    )
    (net (code "95") (name "unconnected-(IC1-PD9-Pad78)") (class "Default")
      (node (ref "IC1") (pin "78") (pinfunction "PD9_78") (pintype "bidirectional"))
    )
    (net (code "96") (name "unconnected-(IC1-PD10-Pad79)") (class "Default")
      (node (ref "IC1") (pin "79") (pinfunction "PD10_79") (pintype "bidirectional"))
    )
    (net (code "97") (name "unconnected-(IC1-PD11-Pad80)") (class "Default")
      (node (ref "IC1") (pin "80") (pinfunction "PD11_80") (pintype "bidirectional"))
    )
    (net (code "98") (name "unconnected-(IC1-PD12-Pad81)") (class "Default")
      (node (ref "IC1") (pin "81") (pinfunction "PD12_81") (pintype "bidirectional"))
    )
    (net (code "99") (name "unconnected-(IC1-PD13-Pad82)") (class "Default")
      (node (ref "IC1") (pin "82") (pinfunction "PD13_82") (pintype "bidirectional"))
    )
    (net (code "100") (name "unconnected-(IC1-PD14-Pad85)") (class "Default")
      (node (ref "IC1") (pin "85") (pinfunction "PD14_85") (pintype "bidirectional"))
    )
    (net (code "101") (name "unconnected-(IC1-PD15-Pad86)") (class "Default")
      (node (ref "IC1") (pin "86") (pinfunction "PD15_86") (pintype "bidirectional"))
    )
    (net (code "102") (name "unconnected-(IC1-PDO-Pad114)") (class "Default")
      (node (ref "IC1") (pin "114") (pinfunction "PDO_114") (pintype "bidirectional"))
    )
    (net (code "103") (name "unconnected-(IC1-PDR_ON-Pad143)") (class "Default")
      (node (ref "IC1") (pin "143") (pinfunction "PDR_ON_143") (pintype "bidirectional"))
    )
    (net (code "104") (name "unconnected-(IC1-PE1-Pad142)") (class "Default")
      (node (ref "IC1") (pin "142") (pinfunction "PE1_142") (pintype "bidirectional"))
    )
    (net (code "105") (name "unconnected-(IC1-PE5-Pad4)") (class "Default")
      (node (ref "IC1") (pin "4") (pinfunction "PE5_4") (pintype "bidirectional"))
    )
    (net (code "106") (name "unconnected-(IC1-PE11-Pad64)") (class "Default")
      (node (ref "IC1") (pin "64") (pinfunction "PE11_64") (pintype "bidirectional"))
    )
    (net (code "107") (name "unconnected-(IC1-PE12-Pad65)") (class "Default")
      (node (ref "IC1") (pin "65") (pinfunction "PE12_65") (pintype "bidirectional"))
    )
    (net (code "108") (name "unconnected-(IC1-PE13-Pad66)") (class "Default")
      (node (ref "IC1") (pin "66") (pinfunction "PE13_66") (pintype "bidirectional"))
    )
    (net (code "109") (name "unconnected-(IC1-PE14-Pad67)") (class "Default")
      (node (ref "IC1") (pin "67") (pinfunction "PE14_67") (pintype "bidirectional"))
    )
    (net (code "110") (name "unconnected-(IC1-PE15-Pad68)") (class "Default")
      (node (ref "IC1") (pin "68") (pinfunction "PE15_68") (pintype "bidirectional"))
    )
    (net (code "111") (name "unconnected-(IC1-PEO-Pad141)") (class "Default")
      (node (ref "IC1") (pin "141") (pinfunction "PEO_141") (pintype "bidirectional"))
    )
    (net (code "112") (name "unconnected-(IC1-PF1-Pad11)") (class "Default")
      (node (ref "IC1") (pin "11") (pinfunction "PF1_11") (pintype "bidirectional"))
    )
    (net (code "113") (name "unconnected-(IC1-PF2-Pad12)") (class "Default")
      (node (ref "IC1") (pin "12") (pinfunction "PF2_12") (pintype "bidirectional"))
    )
    (net (code "114") (name "unconnected-(IC1-PF3-Pad13)") (class "Default")
      (node (ref "IC1") (pin "13") (pinfunction "PF3_13") (pintype "bidirectional"))
    )
    (net (code "115") (name "unconnected-(IC1-PF4-Pad14)") (class "Default")
      (node (ref "IC1") (pin "14") (pinfunction "PF4_14") (pintype "bidirectional"))
    )
    (net (code "116") (name "unconnected-(IC1-PF5-Pad15)") (class "Default")
      (node (ref "IC1") (pin "15") (pinfunction "PF5_15") (pintype "bidirectional"))
    )
    (net (code "117") (name "unconnected-(IC1-PF7-Pad19)") (class "Default")
      (node (ref "IC1") (pin "19") (pinfunction "PF7_19") (pintype "bidirectional"))
    )
    (net (code "118") (name "unconnected-(IC1-PF8-Pad20)") (class "Default")
      (node (ref "IC1") (pin "20") (pinfunction "PF8_20") (pintype "bidirectional"))
    )
    (net (code "119") (name "unconnected-(IC1-PF9-Pad21)") (class "Default")
      (node (ref "IC1") (pin "21") (pinfunction "PF9_21") (pintype "bidirectional"))
    )
    (net (code "120") (name "unconnected-(IC1-PF10-Pad22)") (class "Default")
      (node (ref "IC1") (pin "22") (pinfunction "PF10_22") (pintype "bidirectional"))
    )
    (net (code "121") (name "unconnected-(IC1-PF11-Pad49)") (class "Default")
      (node (ref "IC1") (pin "49") (pinfunction "PF11_49") (pintype "bidirectional"))
    )
    (net (code "122") (name "unconnected-(IC1-PF12-Pad50)") (class "Default")
      (node (ref "IC1") (pin "50") (pinfunction "PF12_50") (pintype "bidirectional"))
    )
    (net (code "123") (name "unconnected-(IC1-PF13-Pad53)") (class "Default")
      (node (ref "IC1") (pin "53") (pinfunction "PF13_53") (pintype "bidirectional"))
    )
    (net (code "124") (name "unconnected-(IC1-PF14-Pad54)") (class "Default")
      (node (ref "IC1") (pin "54") (pinfunction "PF14_54") (pintype "bidirectional"))
    )
    (net (code "125") (name "unconnected-(IC1-PF15-Pad55)") (class "Default")
      (node (ref "IC1") (pin "55") (pinfunction "PF15_55") (pintype "bidirectional"))
    )
    (net (code "126") (name "unconnected-(IC1-PFO-Pad10)") (class "Default")
      (node (ref "IC1") (pin "10") (pinfunction "PFO_10") (pintype "bidirectional"))
    )
    (net (code "127") (name "unconnected-(IC1-PG1-Pad57)") (class "Default")
      (node (ref "IC1") (pin "57") (pinfunction "PG1_57") (pintype "bidirectional"))
    )
    (net (code "128") (name "unconnected-(IC1-PG2-Pad87)") (class "Default")
      (node (ref "IC1") (pin "87") (pinfunction "PG2_87") (pintype "bidirectional"))
    )
    (net (code "129") (name "unconnected-(IC1-PG3-Pad88)") (class "Default")
      (node (ref "IC1") (pin "88") (pinfunction "PG3_88") (pintype "bidirectional"))
    )
    (net (code "130") (name "unconnected-(IC1-PG4-Pad89)") (class "Default")
      (node (ref "IC1") (pin "89") (pinfunction "PG4_89") (pintype "bidirectional"))
    )
    (net (code "131") (name "unconnected-(IC1-PG5-Pad90)") (class "Default")
      (node (ref "IC1") (pin "90") (pinfunction "PG5_90") (pintype "bidirectional"))
    )
    (net (code "132") (name "unconnected-(IC1-PG6-Pad91)") (class "Default")
      (node (ref "IC1") (pin "91") (pinfunction "PG6_91") (pintype "bidirectional"))
    )
    (net (code "133") (name "unconnected-(IC1-PG7-Pad92)") (class "Default")
      (node (ref "IC1") (pin "92") (pinfunction "PG7_92") (pintype "bidirectional"))
    )
    (net (code "134") (name "unconnected-(IC1-PG8-Pad93)") (class "Default")
      (node (ref "IC1") (pin "93") (pinfunction "PG8_93") (pintype "bidirectional"))
    )
    (net (code "135") (name "unconnected-(IC1-PG9-Pad124)") (class "Default")
      (node (ref "IC1") (pin "124") (pinfunction "PG9_124") (pintype "bidirectional"))
    )
    (net (code "136") (name "unconnected-(IC1-PG10-Pad125)") (class "Default")
      (node (ref "IC1") (pin "125") (pinfunction "PG10_125") (pintype "bidirectional"))
    )
    (net (code "137") (name "unconnected-(IC1-PG11-Pad126)") (class "Default")
      (node (ref "IC1") (pin "126") (pinfunction "PG11_126") (pintype "bidirectional"))
    )
    (net (code "138") (name "unconnected-(IC1-PG12-Pad127)") (class "Default")
      (node (ref "IC1") (pin "127") (pinfunction "PG12_127") (pintype "bidirectional"))
    )
    (net (code "139") (name "unconnected-(IC1-PG13-Pad128)") (class "Default")
      (node (ref "IC1") (pin "128") (pinfunction "PG13_128") (pintype "bidirectional"))
    )
    (net (code "140") (name "unconnected-(IC1-PG14-Pad129)") (class "Default")
      (node (ref "IC1") (pin "129") (pinfunction "PG14_129") (pintype "bidirectional"))
    )
    (net (code "141") (name "unconnected-(IC1-PG15-Pad132)") (class "Default")
      (node (ref "IC1") (pin "132") (pinfunction "PG15_132") (pintype "bidirectional"))
    )
    (net (code "142") (name "unconnected-(IC1-PGO-Pad56)") (class "Default")
      (node (ref "IC1") (pin "56") (pinfunction "PGO_56") (pintype "bidirectional"))
    )
    (net (code "143") (name "unconnected-(IC1-VBAT-Pad6)") (class "Default")
      (node (ref "IC1") (pin "6") (pinfunction "VBAT_6") (pintype "bidirectional"))
    )
    (net (code "144") (name "unconnected-(J2-KEY-Pad7)") (class "Default")
      (node (ref "J2") (pin "7") (pinfunction "KEY_7") (pintype "bidirectional"))
    )
    (net (code "145") (name "unconnected-(J2-NC{slash}TDI-Pad8)") (class "Default")
      (node (ref "J2") (pin "8") (pinfunction "NC/TDI_8") (pintype "bidirectional"))
    )
    (net (code "146") (name "unconnected-(LCDCONNECTORB-KL-Pad10)") (class "Default")
      (node (ref "LCDCONNECTOR") (pin "10") (pinfunction "KL_10") (pintype "passive"))
    )
    (net (code "147") (name "unconnected-(LCDCONNECTORE-KL-Pad13)") (class "Default")
      (node (ref "LCDCONNECTOR") (pin "13") (pinfunction "KL_13") (pintype "passive"))
    )
    (net (code "148") (name "unconnected-(LCDCONNECTORF-KL-Pad14)") (class "Default")
      (node (ref "LCDCONNECTOR") (pin "14") (pinfunction "KL_14") (pintype "passive"))
    )
    (net (code "149") (name "unconnected-(LCDCONNECTORG-KL-Pad15)") (class "Default")
      (node (ref "LCDCONNECTOR") (pin "15") (pinfunction "KL_15") (pintype "passive"))
    )
    (net (code "150") (name "unconnected-(LCDCONNECTORH-KL-Pad16)") (class "Default")
      (node (ref "LCDCONNECTOR") (pin "16") (pinfunction "KL_16") (pintype "passive"))
    )
    (net (code "151") (name "unconnected-(LCDCONNECTORR-KL-Pad7)") (class "Default")
      (node (ref "LCDCONNECTOR") (pin "7") (pinfunction "KL_7") (pintype "passive"))
    )
    (net (code "152") (name "unconnected-(LCDCONNECTORT-KL-Pad9)") (class "Default")
      (node (ref "LCDCONNECTOR") (pin "9") (pinfunction "KL_9") (pintype "passive"))
    )
    (net (code "153") (name "unconnected-(P1-Pad2)") (class "Default")
      (node (ref "P1") (pin "2") (pinfunction "2_2") (pintype "passive"))
    )
    (net (code "154") (name "unconnected-(P1-Pad3)") (class "Default")
      (node (ref "P1") (pin "3") (pinfunction "3_3") (pintype "passive"))
    )
    (net (code "155") (name "unconnected-(P1-Pad4)") (class "Default")
      (node (ref "P1") (pin "4") (pinfunction "4_4") (pintype "passive"))
    )
    (net (code "156") (name "unconnected-(P1-Pad5)") (class "Default")
      (node (ref "P1") (pin "5") (pinfunction "5_5") (pintype "passive"))
    )
    (net (code "157") (name "unconnected-(P1-Pad6)") (class "Default")
      (node (ref "P1") (pin "6") (pinfunction "6_6") (pintype "passive"))
    )
    (net (code "158") (name "unconnected-(P1-Pad9)") (class "Default")
      (node (ref "P1") (pin "9") (pinfunction "9_9") (pintype "passive"))
    )
    (net (code "159") (name "unconnected-(P1-Pad10)") (class "Default")
      (node (ref "P1") (pin "10") (pinfunction "10_10") (pintype "passive"))
    )
    (net (code "160") (name "unconnected-(P1-Pad11)") (class "Default")
      (node (ref "P1") (pin "11") (pinfunction "11_11") (pintype "passive"))
    )
    (net (code "161") (name "unconnected-(P1-Pad12)") (class "Default")
      (node (ref "P1") (pin "12") (pinfunction "12_12") (pintype "passive"))
    )
    (net (code "162") (name "unconnected-(P1-Pad15)") (class "Default")
      (node (ref "P1") (pin "15") (pinfunction "15_15") (pintype "passive"))
    )
    (net (code "163") (name "unconnected-(P1-Pad16)") (class "Default")
      (node (ref "P1") (pin "16") (pinfunction "16_16") (pintype "passive"))
    )
    (net (code "164") (name "unconnected-(P1-Pad17)") (class "Default")
      (node (ref "P1") (pin "17") (pinfunction "17_17") (pintype "passive"))
    )
    (net (code "165") (name "unconnected-(P1-Pad18)") (class "Default")
      (node (ref "P1") (pin "18") (pinfunction "18_18") (pintype "passive"))
    )
    (net (code "166") (name "unconnected-(P1-Pad21)") (class "Default")
      (node (ref "P1") (pin "21") (pinfunction "21_21") (pintype "passive"))
    )
    (net (code "167") (name "unconnected-(P1-Pad22)") (class "Default")
      (node (ref "P1") (pin "22") (pinfunction "22_22") (pintype "passive"))
    )
    (net (code "168") (name "unconnected-(P1-Pad23)") (class "Default")
      (node (ref "P1") (pin "23") (pinfunction "23_23") (pintype "passive"))
    )
    (net (code "169") (name "unconnected-(P1-Pad24)") (class "Default")
      (node (ref "P1") (pin "24") (pinfunction "24_24") (pintype "passive"))
    )
    (net (code "170") (name "unconnected-(P1-Pad27)") (class "Default")
      (node (ref "P1") (pin "27") (pinfunction "27_27") (pintype "passive"))
    )
    (net (code "171") (name "unconnected-(P1-Pad28)") (class "Default")
      (node (ref "P1") (pin "28") (pinfunction "28_28") (pintype "passive"))
    )
    (net (code "172") (name "unconnected-(P1-Pad29)") (class "Default")
      (node (ref "P1") (pin "29") (pinfunction "29_29") (pintype "passive"))
    )
    (net (code "173") (name "unconnected-(P1-Pad30)") (class "Default")
      (node (ref "P1") (pin "30") (pinfunction "30_30") (pintype "passive"))
    )
    (net (code "174") (name "unconnected-(P1-Pad33)") (class "Default")
      (node (ref "P1") (pin "33") (pinfunction "33_33") (pintype "passive"))
    )
    (net (code "175") (name "unconnected-(P1-Pad34)") (class "Default")
      (node (ref "P1") (pin "34") (pinfunction "34_34") (pintype "passive"))
    )
    (net (code "176") (name "unconnected-(P1-Pad35)") (class "Default")
      (node (ref "P1") (pin "35") (pinfunction "35_35") (pintype "passive"))
    )
    (net (code "177") (name "unconnected-(P1-Pad36)") (class "Default")
      (node (ref "P1") (pin "36") (pinfunction "36_36") (pintype "passive"))
    )
    (net (code "178") (name "unconnected-(P1-Pad39)") (class "Default")
      (node (ref "P1") (pin "39") (pinfunction "39_39") (pintype "passive"))
    )
    (net (code "179") (name "unconnected-(P1-Pad40)") (class "Default")
      (node (ref "P1") (pin "40") (pinfunction "40_40") (pintype "passive"))
    )
    (net (code "180") (name "unconnected-(P1-Pad41)") (class "Default")
      (node (ref "P1") (pin "41") (pinfunction "41_41") (pintype "passive"))
    )
    (net (code "181") (name "unconnected-(P1-Pad42)") (class "Default")
      (node (ref "P1") (pin "42") (pinfunction "42_42") (pintype "passive"))
    )
    (net (code "182") (name "unconnected-(P1-Pad45)") (class "Default")
      (node (ref "P1") (pin "45") (pinfunction "45_45") (pintype "passive"))
    )
    (net (code "183") (name "unconnected-(P1-Pad46)") (class "Default")
      (node (ref "P1") (pin "46") (pinfunction "46_46") (pintype "passive"))
    )
    (net (code "184") (name "unconnected-(P1-Pad47)") (class "Default")
      (node (ref "P1") (pin "47") (pinfunction "47_47") (pintype "passive"))
    )
    (net (code "185") (name "unconnected-(P1-Pad48)") (class "Default")
      (node (ref "P1") (pin "48") (pinfunction "48_48") (pintype "passive"))
    )
    (net (code "186") (name "unconnected-(P1-Pad52)") (class "Default")
      (node (ref "P1") (pin "52") (pinfunction "52_52") (pintype "passive"))
    )
    (net (code "187") (name "unconnected-(P1-Pad54)") (class "Default")
      (node (ref "P1") (pin "54") (pinfunction "54_54") (pintype "passive"))
    )
    (net (code "188") (name "unconnected-(P1-Pad57)") (class "Default")
      (node (ref "P1") (pin "57") (pinfunction "57_57") (pintype "passive"))
    )
    (net (code "189") (name "unconnected-(P1-Pad58)") (class "Default")
      (node (ref "P1") (pin "58") (pinfunction "58_58") (pintype "passive"))
    )
    (net (code "190") (name "unconnected-(P1-Pad59)") (class "Default")
      (node (ref "P1") (pin "59") (pinfunction "59_59") (pintype "passive"))
    )
    (net (code "191") (name "unconnected-(P1-Pad60)") (class "Default")
      (node (ref "P1") (pin "60") (pinfunction "60_60") (pintype "passive"))
    )
    (net (code "192") (name "unconnected-(P1-Pad63)") (class "Default")
      (node (ref "P1") (pin "63") (pinfunction "63_63") (pintype "passive"))
    )
    (net (code "193") (name "unconnected-(P1-Pad64)") (class "Default")
      (node (ref "P1") (pin "64") (pinfunction "64_64") (pintype "passive"))
    )
    (net (code "194") (name "unconnected-(P1-Pad65)") (class "Default")
      (node (ref "P1") (pin "65") (pinfunction "65_65") (pintype "passive"))
    )
    (net (code "195") (name "unconnected-(P1-Pad66)") (class "Default")
      (node (ref "P1") (pin "66") (pinfunction "66_66") (pintype "passive"))
    )
    (net (code "196") (name "unconnected-(P1-Pad69)") (class "Default")
      (node (ref "P1") (pin "69") (pinfunction "69_69") (pintype "passive"))
    )
    (net (code "197") (name "unconnected-(P1-Pad70)") (class "Default")
      (node (ref "P1") (pin "70") (pinfunction "70_70") (pintype "passive"))
    )
    (net (code "198") (name "unconnected-(P1-Pad71)") (class "Default")
      (node (ref "P1") (pin "71") (pinfunction "71_71") (pintype "passive"))
    )
    (net (code "199") (name "unconnected-(P1-Pad72)") (class "Default")
      (node (ref "P1") (pin "72") (pinfunction "72_72") (pintype "passive"))
    )
    (net (code "200") (name "unconnected-(P1-Pad75)") (class "Default")
      (node (ref "P1") (pin "75") (pinfunction "75_75") (pintype "passive"))
    )
    (net (code "201") (name "unconnected-(P1-Pad76)") (class "Default")
      (node (ref "P1") (pin "76") (pinfunction "76_76") (pintype "passive"))
    )
    (net (code "202") (name "unconnected-(P1-Pad77)") (class "Default")
      (node (ref "P1") (pin "77") (pinfunction "77_77") (pintype "passive"))
    )
    (net (code "203") (name "unconnected-(P1-Pad78)") (class "Default")
      (node (ref "P1") (pin "78") (pinfunction "78_78") (pintype "passive"))
    )
    (net (code "204") (name "unconnected-(P1-Pad81)") (class "Default")
      (node (ref "P1") (pin "81") (pinfunction "81_81") (pintype "passive"))
    )
    (net (code "205") (name "unconnected-(P1-Pad82)") (class "Default")
      (node (ref "P1") (pin "82") (pinfunction "82_82") (pintype "passive"))
    )
    (net (code "206") (name "unconnected-(P1-Pad83)") (class "Default")
      (node (ref "P1") (pin "83") (pinfunction "83_83") (pintype "passive"))
    )
    (net (code "207") (name "unconnected-(P1-Pad84)") (class "Default")
      (node (ref "P1") (pin "84") (pinfunction "84_84") (pintype "passive"))
    )
    (net (code "208") (name "unconnected-(P1-Pad87)") (class "Default")
      (node (ref "P1") (pin "87") (pinfunction "87_87") (pintype "passive"))
    )
    (net (code "209") (name "unconnected-(P1-Pad88)") (class "Default")
      (node (ref "P1") (pin "88") (pinfunction "88_88") (pintype "passive"))
    )
    (net (code "210") (name "unconnected-(P1-Pad89)") (class "Default")
      (node (ref "P1") (pin "89") (pinfunction "89_89") (pintype "passive"))
    )
    (net (code "211") (name "unconnected-(P1-Pad90)") (class "Default")
      (node (ref "P1") (pin "90") (pinfunction "90_90") (pintype "passive"))
    )
    (net (code "212") (name "unconnected-(P1-Pad93)") (class "Default")
      (node (ref "P1") (pin "93") (pinfunction "93_93") (pintype "passive"))
    )
    (net (code "213") (name "unconnected-(P1-Pad94)") (class "Default")
      (node (ref "P1") (pin "94") (pinfunction "94_94") (pintype "passive"))
    )
    (net (code "214") (name "unconnected-(P1-Pad95)") (class "Default")
      (node (ref "P1") (pin "95") (pinfunction "95_95") (pintype "passive"))
    )
    (net (code "215") (name "unconnected-(P1-Pad96)") (class "Default")
      (node (ref "P1") (pin "96") (pinfunction "96_96") (pintype "passive"))
    )
    (net (code "216") (name "unconnected-(P1-Pad99)") (class "Default")
      (node (ref "P1") (pin "99") (pinfunction "99_99") (pintype "passive"))
    )
    (net (code "217") (name "unconnected-(P1-Pad100)") (class "Default")
      (node (ref "P1") (pin "100") (pinfunction "100_100") (pintype "passive"))
    )
    (net (code "218") (name "unconnected-(P1-Pad101)") (class "Default")
      (node (ref "P1") (pin "101") (pinfunction "101_101") (pintype "passive"))
    )
    (net (code "219") (name "unconnected-(P1-Pad102)") (class "Default")
      (node (ref "P1") (pin "102") (pinfunction "102_102") (pintype "passive"))
    )
    (net (code "220") (name "unconnected-(P1-Pad105)") (class "Default")
      (node (ref "P1") (pin "105") (pinfunction "105_105") (pintype "passive"))
    )
    (net (code "221") (name "unconnected-(P1-Pad106)") (class "Default")
      (node (ref "P1") (pin "106") (pinfunction "106_106") (pintype "passive"))
    )
    (net (code "222") (name "unconnected-(P1-Pad107)") (class "Default")
      (node (ref "P1") (pin "107") (pinfunction "107_107") (pintype "passive"))
    )
    (net (code "223") (name "unconnected-(P1-Pad108)") (class "Default")
      (node (ref "P1") (pin "108") (pinfunction "108_108") (pintype "passive"))
    )
    (net (code "224") (name "unconnected-(P1-Pad111)") (class "Default")
      (node (ref "P1") (pin "111") (pinfunction "111_111") (pintype "passive"))
    )
    (net (code "225") (name "unconnected-(P1-Pad112)") (class "Default")
      (node (ref "P1") (pin "112") (pinfunction "112_112") (pintype "passive"))
    )
    (net (code "226") (name "unconnected-(P1-Pad113)") (class "Default")
      (node (ref "P1") (pin "113") (pinfunction "113_113") (pintype "passive"))
    )
    (net (code "227") (name "unconnected-(P1-Pad114)") (class "Default")
      (node (ref "P1") (pin "114") (pinfunction "114_114") (pintype "passive"))
    )
    (net (code "228") (name "unconnected-(P1-Pad117)") (class "Default")
      (node (ref "P1") (pin "117") (pinfunction "117_117") (pintype "passive"))
    )
    (net (code "229") (name "unconnected-(P1-Pad118)") (class "Default")
      (node (ref "P1") (pin "118") (pinfunction "118_118") (pintype "passive"))
    )
    (net (code "230") (name "unconnected-(P1-Pad119)") (class "Default")
      (node (ref "P1") (pin "119") (pinfunction "119_119") (pintype "passive"))
    )
    (net (code "231") (name "unconnected-(P1-Pad120)") (class "Default")
      (node (ref "P1") (pin "120") (pinfunction "120_120") (pintype "passive"))
    )
    (net (code "232") (name "unconnected-(P1-Pad123)") (class "Default")
      (node (ref "P1") (pin "123") (pinfunction "123_123") (pintype "passive"))
    )
    (net (code "233") (name "unconnected-(P1-Pad124)") (class "Default")
      (node (ref "P1") (pin "124") (pinfunction "124_124") (pintype "passive"))
    )
    (net (code "234") (name "unconnected-(P1-Pad125)") (class "Default")
      (node (ref "P1") (pin "125") (pinfunction "125_125") (pintype "passive"))
    )
    (net (code "235") (name "unconnected-(P1-Pad126)") (class "Default")
      (node (ref "P1") (pin "126") (pinfunction "126_126") (pintype "passive"))
    )
    (net (code "236") (name "unconnected-(P1-Pad128)") (class "Default")
      (node (ref "P1") (pin "128") (pinfunction "128_128") (pintype "passive"))
    )
    (net (code "237") (name "unconnected-(P1-Pad129)") (class "Default")
      (node (ref "P1") (pin "129") (pinfunction "129_129") (pintype "passive"))
    )
    (net (code "238") (name "unconnected-(P1-Pad130)") (class "Default")
      (node (ref "P1") (pin "130") (pinfunction "130_130") (pintype "passive"))
    )
    (net (code "239") (name "unconnected-(P1-Pad131)") (class "Default")
      (node (ref "P1") (pin "131") (pinfunction "131_131") (pintype "passive"))
    )
    (net (code "240") (name "unconnected-(P1-Pad132)") (class "Default")
      (node (ref "P1") (pin "132") (pinfunction "132_132") (pintype "passive"))
    )
    (net (code "241") (name "unconnected-(P1-Pad135)") (class "Default")
      (node (ref "P1") (pin "135") (pinfunction "135_135") (pintype "passive"))
    )
    (net (code "242") (name "unconnected-(P1-Pad136)") (class "Default")
      (node (ref "P1") (pin "136") (pinfunction "136_136") (pintype "passive"))
    )
    (net (code "243") (name "unconnected-(P1-Pad137)") (class "Default")
      (node (ref "P1") (pin "137") (pinfunction "137_137") (pintype "passive"))
    )
    (net (code "244") (name "unconnected-(P1-Pad138)") (class "Default")
      (node (ref "P1") (pin "138") (pinfunction "138_138") (pintype "passive"))
    )
    (net (code "245") (name "unconnected-(P1-Pad141)") (class "Default")
      (node (ref "P1") (pin "141") (pinfunction "141_141") (pintype "passive"))
    )
    (net (code "246") (name "unconnected-(P1-Pad142)") (class "Default")
      (node (ref "P1") (pin "142") (pinfunction "142_142") (pintype "passive"))
    )
    (net (code "247") (name "unconnected-(P1-Pad143)") (class "Default")
      (node (ref "P1") (pin "143") (pinfunction "143_143") (pintype "passive"))
    )
    (net (code "248") (name "unconnected-(P1-Pad144)") (class "Default")
      (node (ref "P1") (pin "144") (pinfunction "144_144") (pintype "passive"))
    )
    (net (code "249") (name "unconnected-(P1-Pad147)") (class "Default")
      (node (ref "P1") (pin "147") (pinfunction "147_147") (pintype "passive"))
    )
    (net (code "250") (name "unconnected-(P1-Pad148)") (class "Default")
      (node (ref "P1") (pin "148") (pinfunction "148_148") (pintype "passive"))
    )
    (net (code "251") (name "unconnected-(P1-Pad149)") (class "Default")
      (node (ref "P1") (pin "149") (pinfunction "149_149") (pintype "passive"))
    )
    (net (code "252") (name "unconnected-(P1-Pad150)") (class "Default")
      (node (ref "P1") (pin "150") (pinfunction "150_150") (pintype "passive"))
    )
    (net (code "253") (name "unconnected-(P1-Pad153)") (class "Default")
      (node (ref "P1") (pin "153") (pinfunction "153_153") (pintype "passive"))
    )
    (net (code "254") (name "unconnected-(P1-Pad154)") (class "Default")
      (node (ref "P1") (pin "154") (pinfunction "154_154") (pintype "passive"))
    )
    (net (code "255") (name "unconnected-(P1-Pad155)") (class "Default")
      (node (ref "P1") (pin "155") (pinfunction "155_155") (pintype "passive"))
    )
    (net (code "256") (name "unconnected-(P1-Pad156)") (class "Default")
      (node (ref "P1") (pin "156") (pinfunction "156_156") (pintype "passive"))
    )
    (net (code "257") (name "unconnected-(P1-Pad158)") (class "Default")
      (node (ref "P1") (pin "158") (pinfunction "158_158") (pintype "passive"))
    )
    (net (code "258") (name "unconnected-(P1-Pad159)") (class "Default")
      (node (ref "P1") (pin "159") (pinfunction "159_159") (pintype "passive"))
    )
    (net (code "259") (name "unconnected-(P1-Pad160)") (class "Default")
      (node (ref "P1") (pin "160") (pinfunction "160_160") (pintype "passive"))
    )
    (net (code "260") (name "unconnected-(P1-Pad161)") (class "Default")
      (node (ref "P1") (pin "161") (pinfunction "161_161") (pintype "passive"))
    )
    (net (code "261") (name "unconnected-(P1-Pad162)") (class "Default")
      (node (ref "P1") (pin "162") (pinfunction "162_162") (pintype "passive"))
    )
    (net (code "262") (name "unconnected-(P1-Pad166)") (class "Default")
      (node (ref "P1") (pin "166") (pinfunction "166_166") (pintype "passive"))
    )
    (net (code "263") (name "unconnected-(P1-Pad171)") (class "Default")
      (node (ref "P1") (pin "171") (pinfunction "171_171") (pintype "passive"))
    )
    (net (code "264") (name "unconnected-(P1-Pad172)") (class "Default")
      (node (ref "P1") (pin "172") (pinfunction "172_172") (pintype "passive"))
    )
    (net (code "265") (name "unconnected-(P1-Pad173)") (class "Default")
      (node (ref "P1") (pin "173") (pinfunction "173_173") (pintype "passive"))
    )
    (net (code "266") (name "unconnected-(P1-Pad174)") (class "Default")
      (node (ref "P1") (pin "174") (pinfunction "174_174") (pintype "passive"))
    )
    (net (code "267") (name "unconnected-(P1-Pad175)") (class "Default")
      (node (ref "P1") (pin "175") (pinfunction "175_175") (pintype "passive"))
    )
    (net (code "268") (name "unconnected-(P1-Pad176)") (class "Default")
      (node (ref "P1") (pin "176") (pinfunction "176_176") (pintype "passive"))
    )
    (net (code "269") (name "unconnected-(P1-Pad178)") (class "Default")
      (node (ref "P1") (pin "178") (pinfunction "178_178") (pintype "passive"))
    )
    (net (code "270") (name "unconnected-(P1-Pad179)") (class "Default")
      (node (ref "P1") (pin "179") (pinfunction "179_179") (pintype "passive"))
    )
    (net (code "271") (name "unconnected-(P1-Pad180)") (class "Default")
      (node (ref "P1") (pin "180") (pinfunction "180_180") (pintype "passive"))
    )
    (net (code "272") (name "unconnected-(P1-Pad189)") (class "Default")
      (node (ref "P1") (pin "189") (pinfunction "189_189") (pintype "passive"))
    )
    (net (code "273") (name "unconnected-(P1-Pad190)") (class "Default")
      (node (ref "P1") (pin "190") (pinfunction "190_190") (pintype "passive"))
    )
    (net (code "274") (name "unconnected-(PROXIMITYSENSOR-Pad4)") (class "Default")
      (node (ref "PROXIMITYSENSOR") (pin "4") (pinfunction "4_4") (pintype "passive"))
    )
    (net (code "275") (name "unconnected-(U1B-NC-Pad19)") (class "Default")
      (node (ref "U1") (pin "19") (pinfunction "NC_19") (pintype "passive"))
    )
    (net (code "276") (name "unconnected-(U1B-NC_2-Pad1)") (class "Default")
      (node (ref "U1") (pin "1") (pinfunction "NC_2_1") (pintype "passive"))
    )
    (net (code "277") (name "unconnected-(U1B-NC_3-Pad2)") (class "Default")
      (node (ref "U1") (pin "2") (pinfunction "NC_3_2") (pintype "passive"))
    )
    (net (code "278") (name "unconnected-(U1B-NC_4-Pad3)") (class "Default")
      (node (ref "U1") (pin "3") (pinfunction "NC_4_3") (pintype "passive"))
    )
    (net (code "279") (name "unconnected-(U1B-NC_5-Pad5)") (class "Default")
      (node (ref "U1") (pin "5") (pinfunction "NC_5_5") (pintype "passive"))
    )
    (net (code "280") (name "unconnected-(U1B-NC_6-Pad7)") (class "Default")
      (node (ref "U1") (pin "7") (pinfunction "NC_6_7") (pintype "passive"))
    )
    (net (code "281") (name "unconnected-(U1B-NC_7-Pad9)") (class "Default")
      (node (ref "U1") (pin "9") (pinfunction "NC_7_9") (pintype "passive"))
    )
    (net (code "282") (name "unconnected-(U1B-NC_8-Pad10)") (class "Default")
      (node (ref "U1") (pin "10") (pinfunction "NC_8_10") (pintype "passive"))
    )
    (net (code "283") (name "unconnected-(U1B-NC_9-Pad11)") (class "Default")
      (node (ref "U1") (pin "11") (pinfunction "NC_9_11") (pintype "passive"))
    )
    (net (code "284") (name "unconnected-(U1B-NC_10-Pad12)") (class "Default")
      (node (ref "U1") (pin "12") (pinfunction "NC_10_12") (pintype "passive"))
    )
    (net (code "285") (name "unconnected-(U1B-NC_11-Pad13)") (class "Default")
      (node (ref "U1") (pin "13") (pinfunction "NC_11_13") (pintype "passive"))
    )
    (net (code "286") (name "unconnected-(U1B-NC_12-Pad14)") (class "Default")
      (node (ref "U1") (pin "14") (pinfunction "NC_12_14") (pintype "passive"))
    )
    (net (code "287") (name "unconnected-(U1B-NC_13-Pad15)") (class "Default")
      (node (ref "U1") (pin "15") (pinfunction "NC_13_15") (pintype "passive"))
    )
    (net (code "288") (name "unconnected-(U1B-NC_14-Pad16)") (class "Default")
      (node (ref "U1") (pin "16") (pinfunction "NC_14_16") (pintype "passive"))
    )
    (net (code "289") (name "unconnected-(U1B-NC_15-Pad17)") (class "Default")
      (node (ref "U1") (pin "17") (pinfunction "NC_15_17") (pintype "passive"))
    )
    (net (code "290") (name "unconnected-(U1B-NC_16-Pad18)") (class "Default")
      (node (ref "U1") (pin "18") (pinfunction "NC_16_18") (pintype "passive"))
    )
  )
)
